# FaderBay.net
KiCad netlist of a schematic drawn in EasyEDA Pro
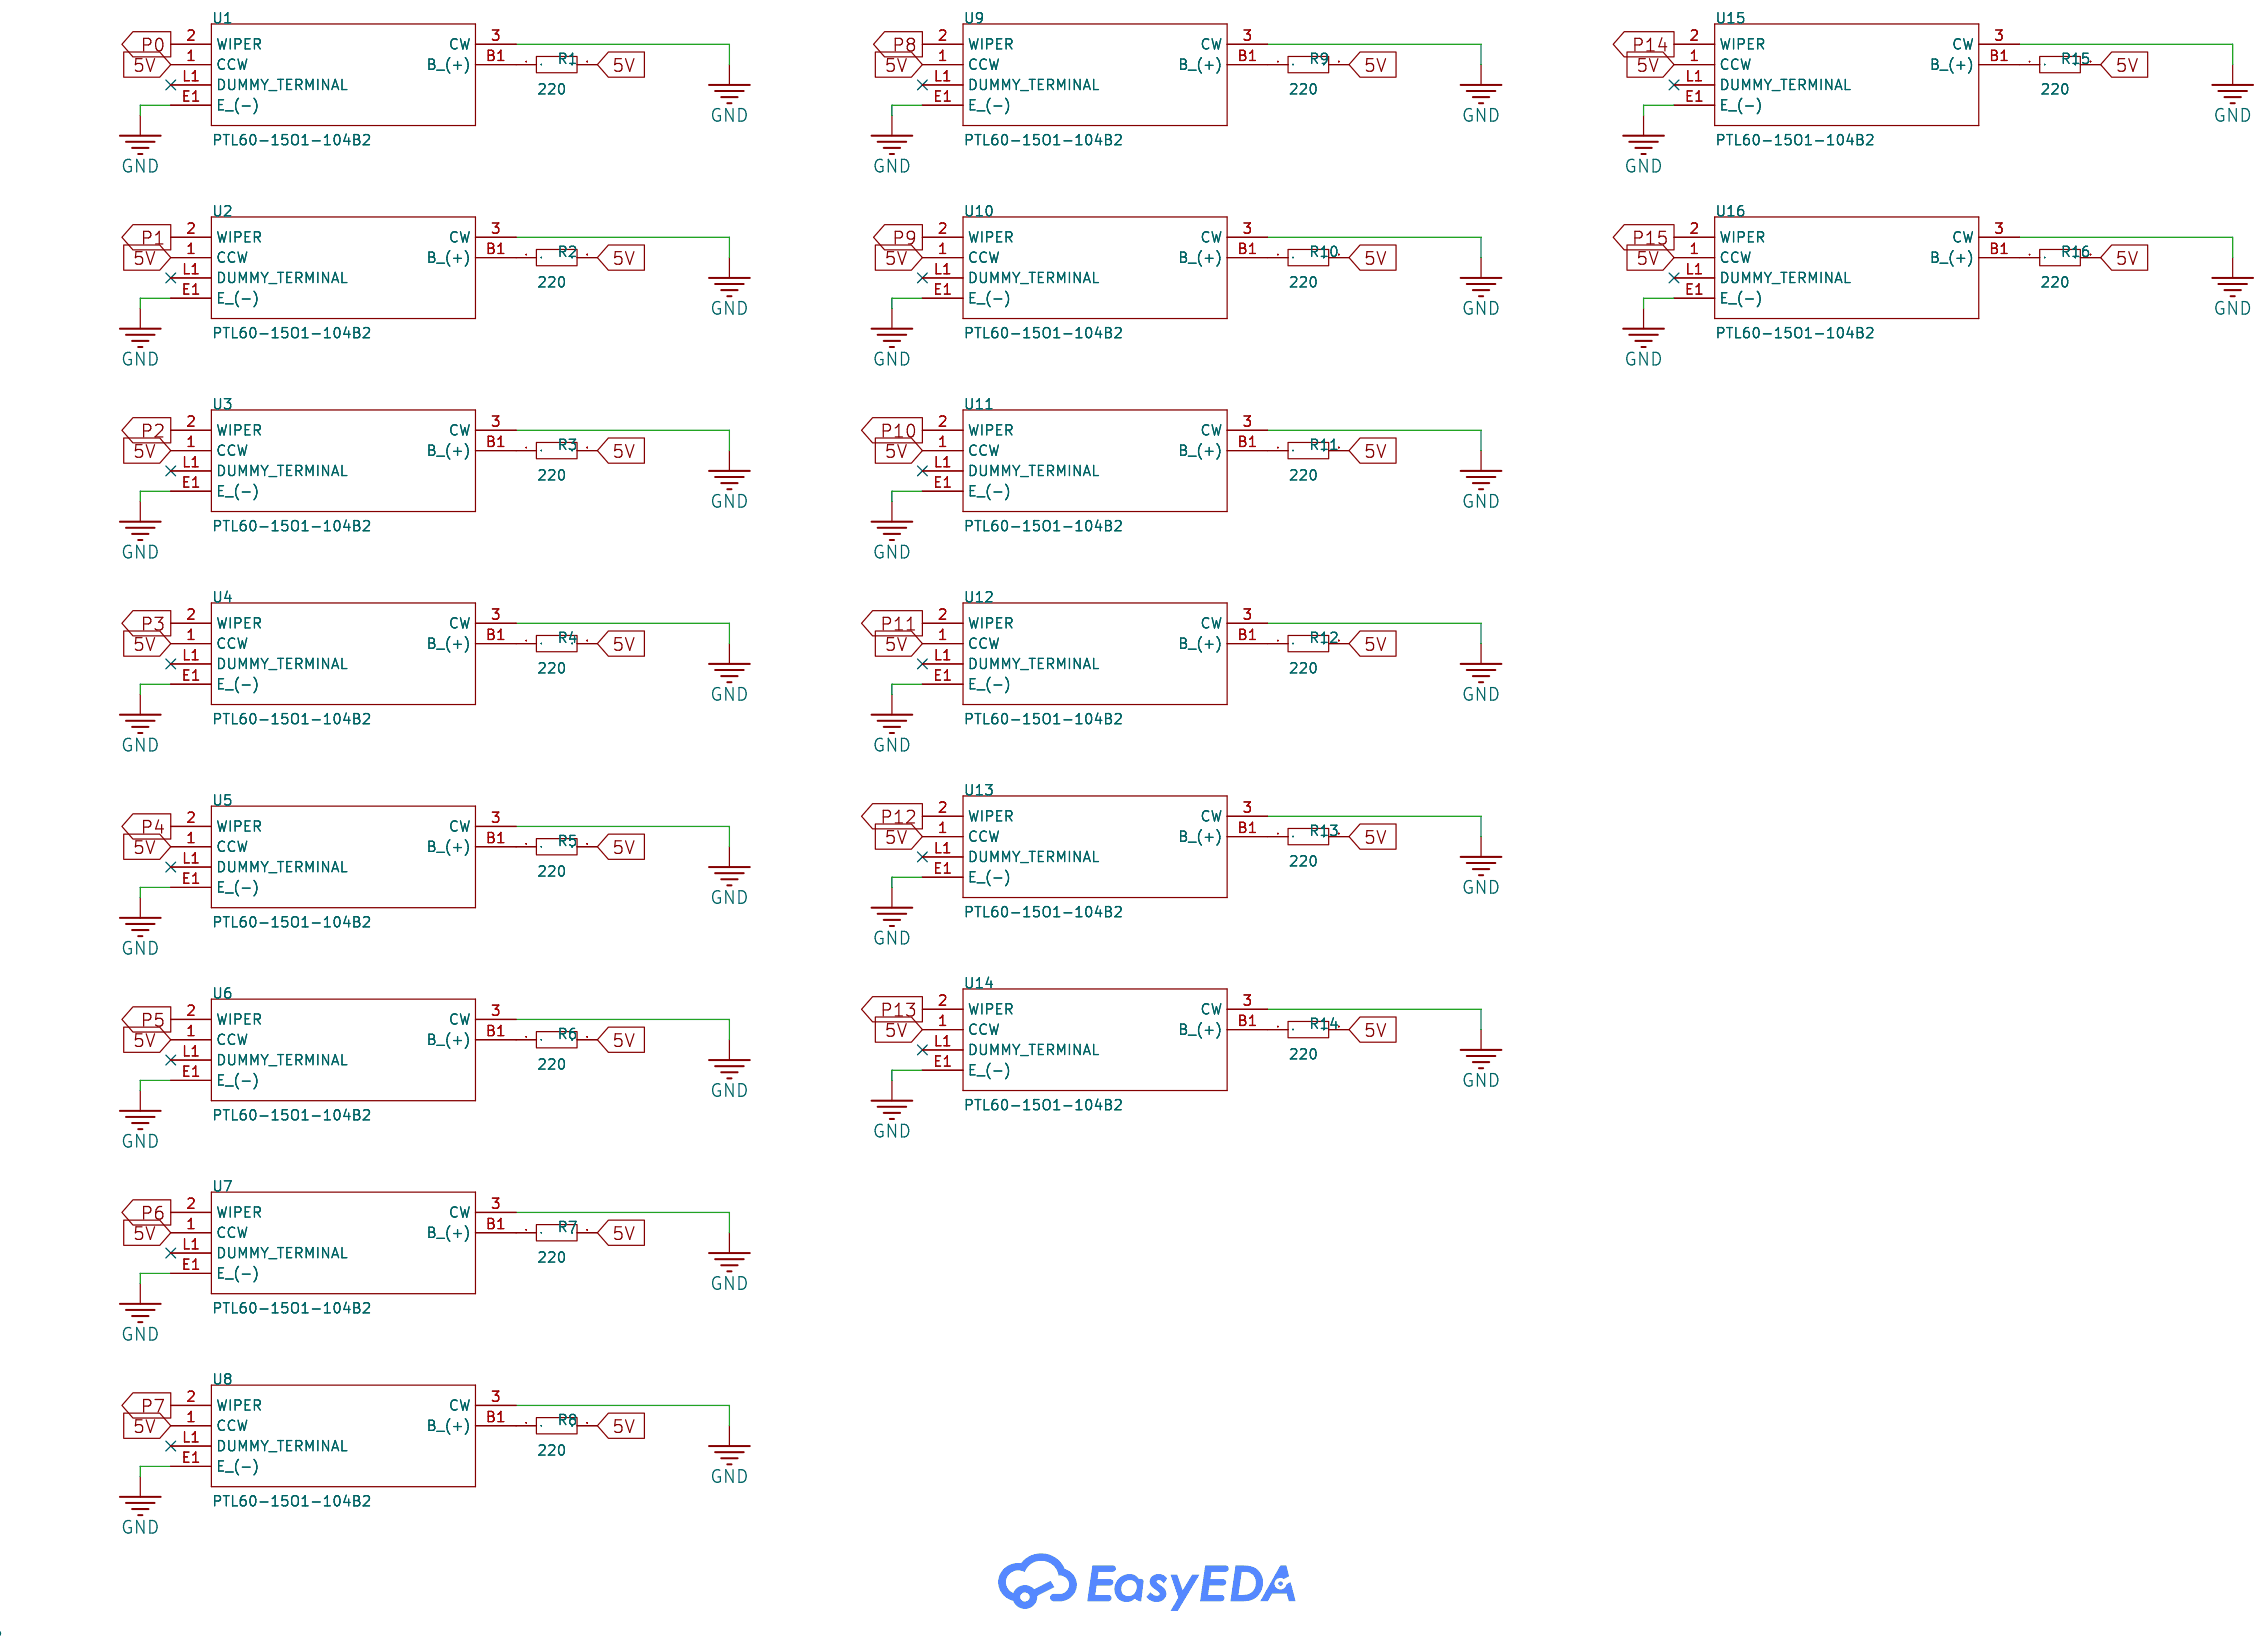
[diagram p0: P1]
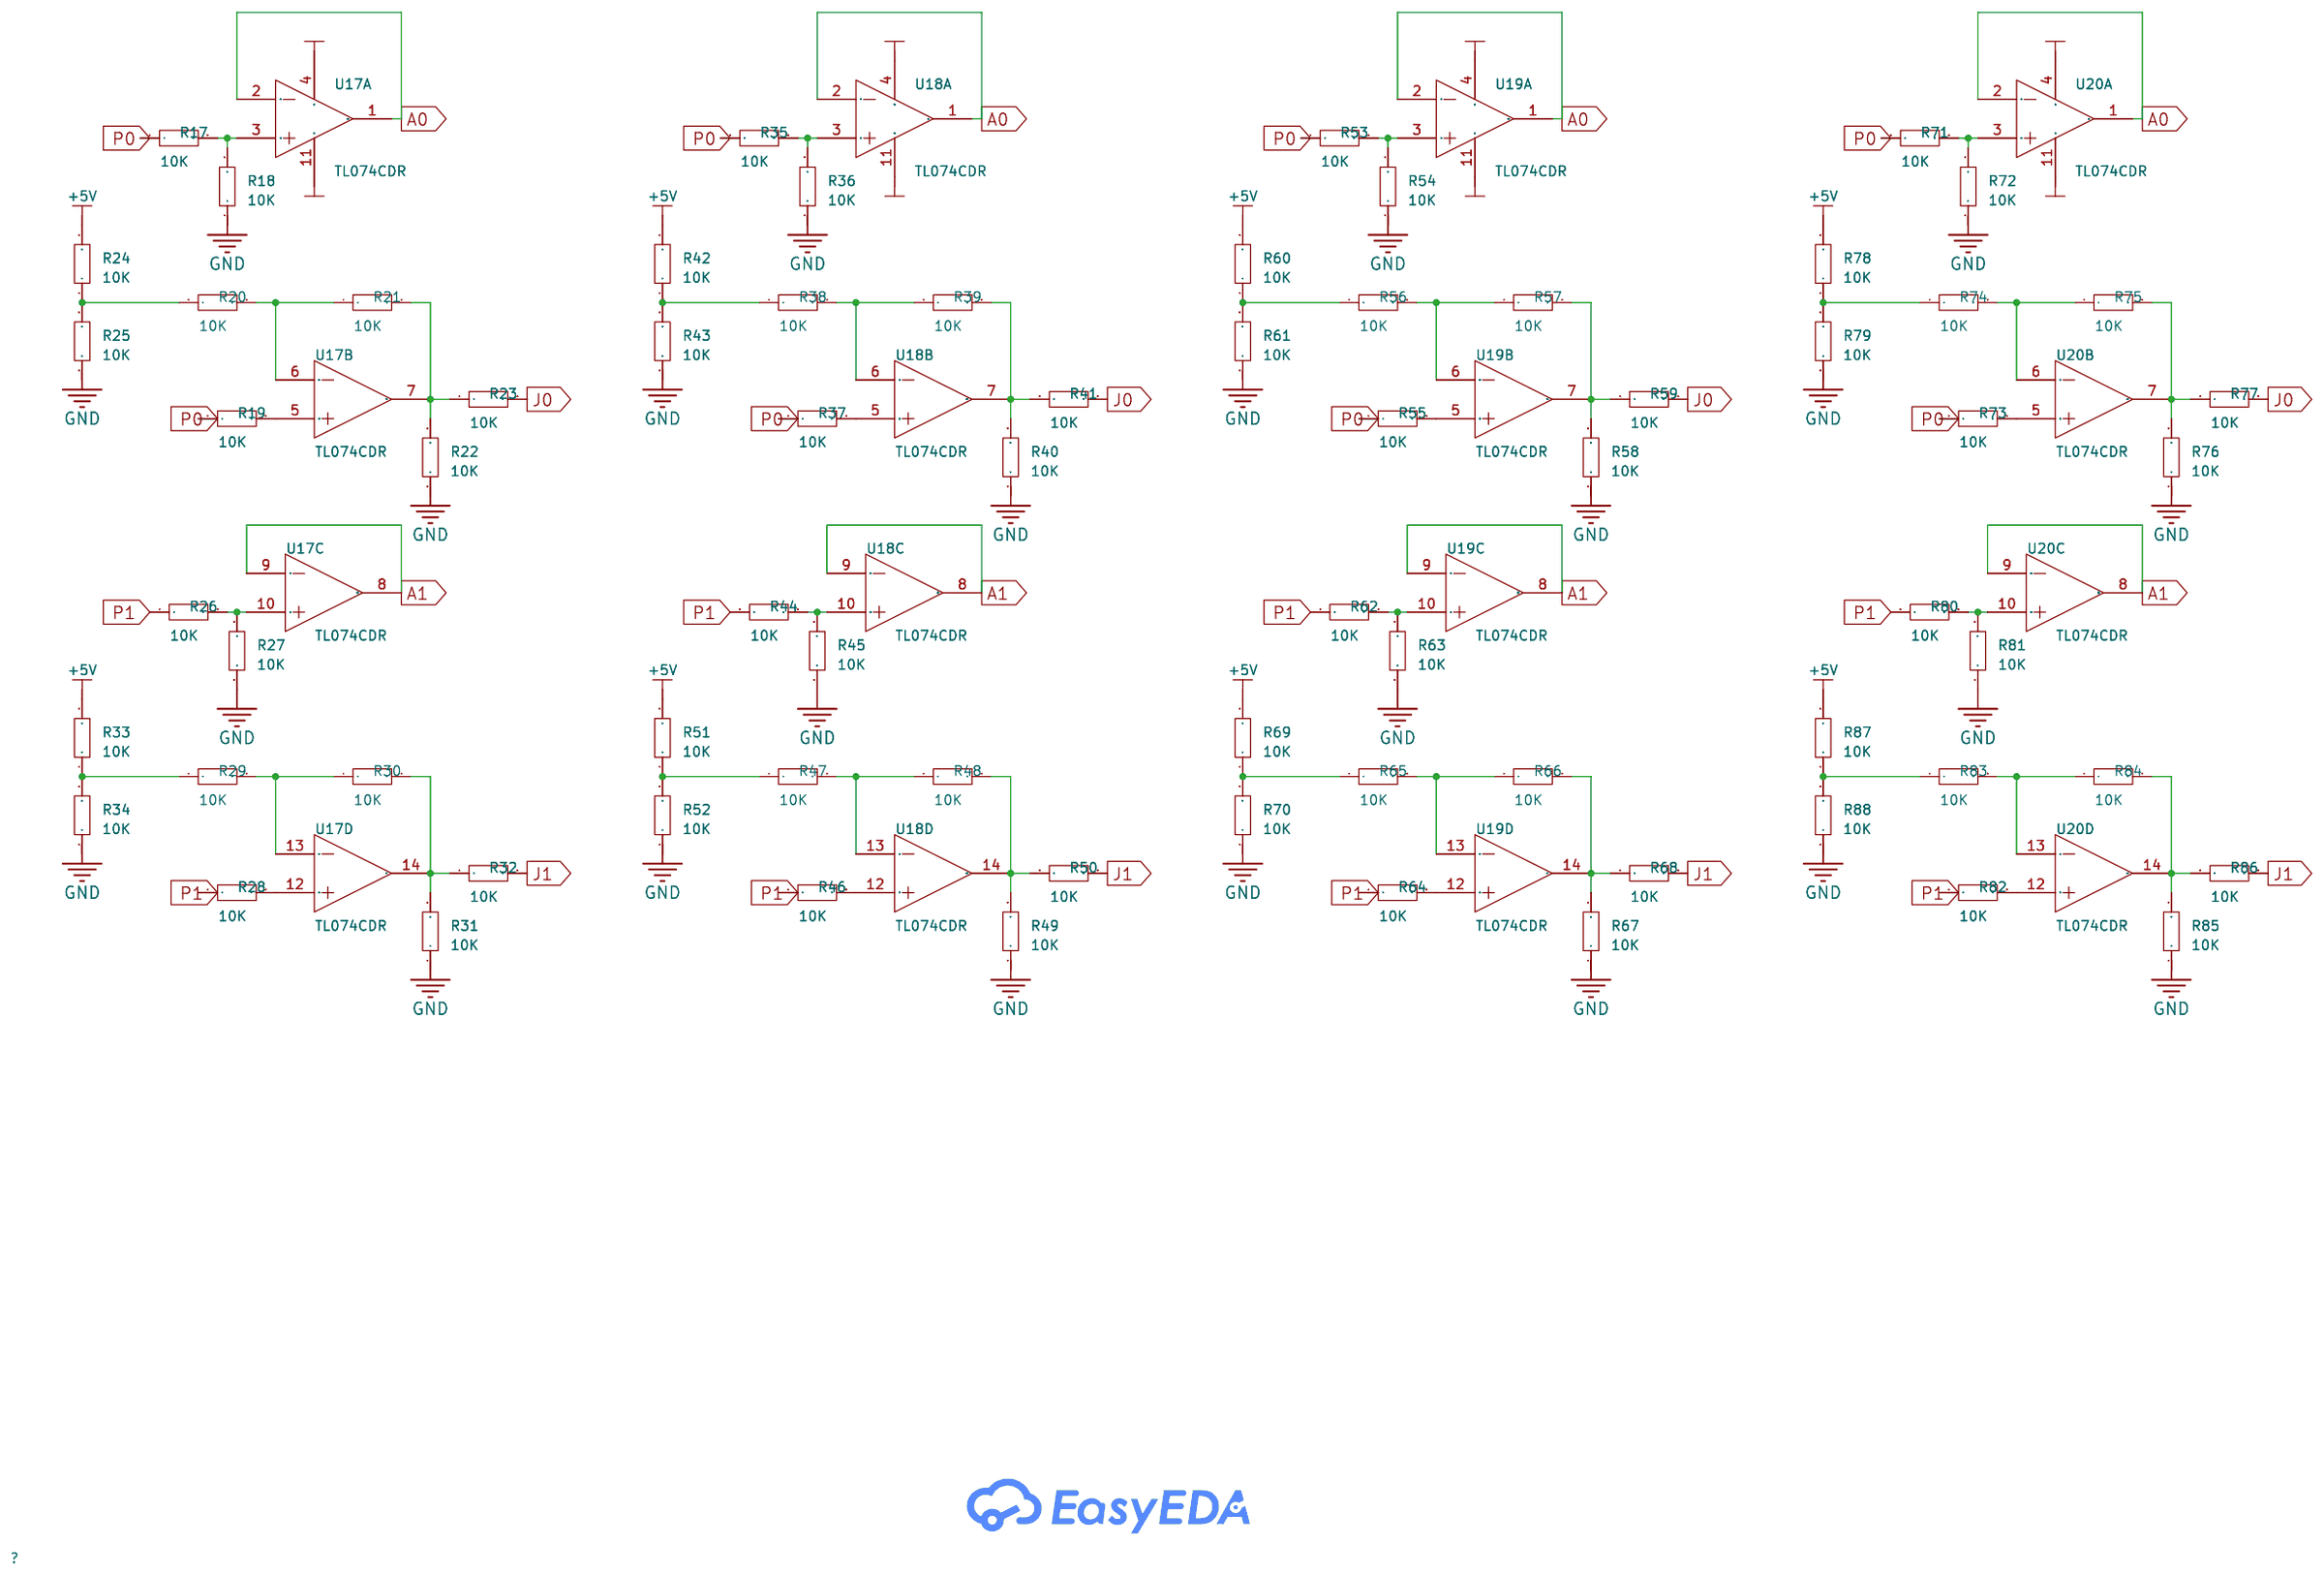
[diagram p1: P2]
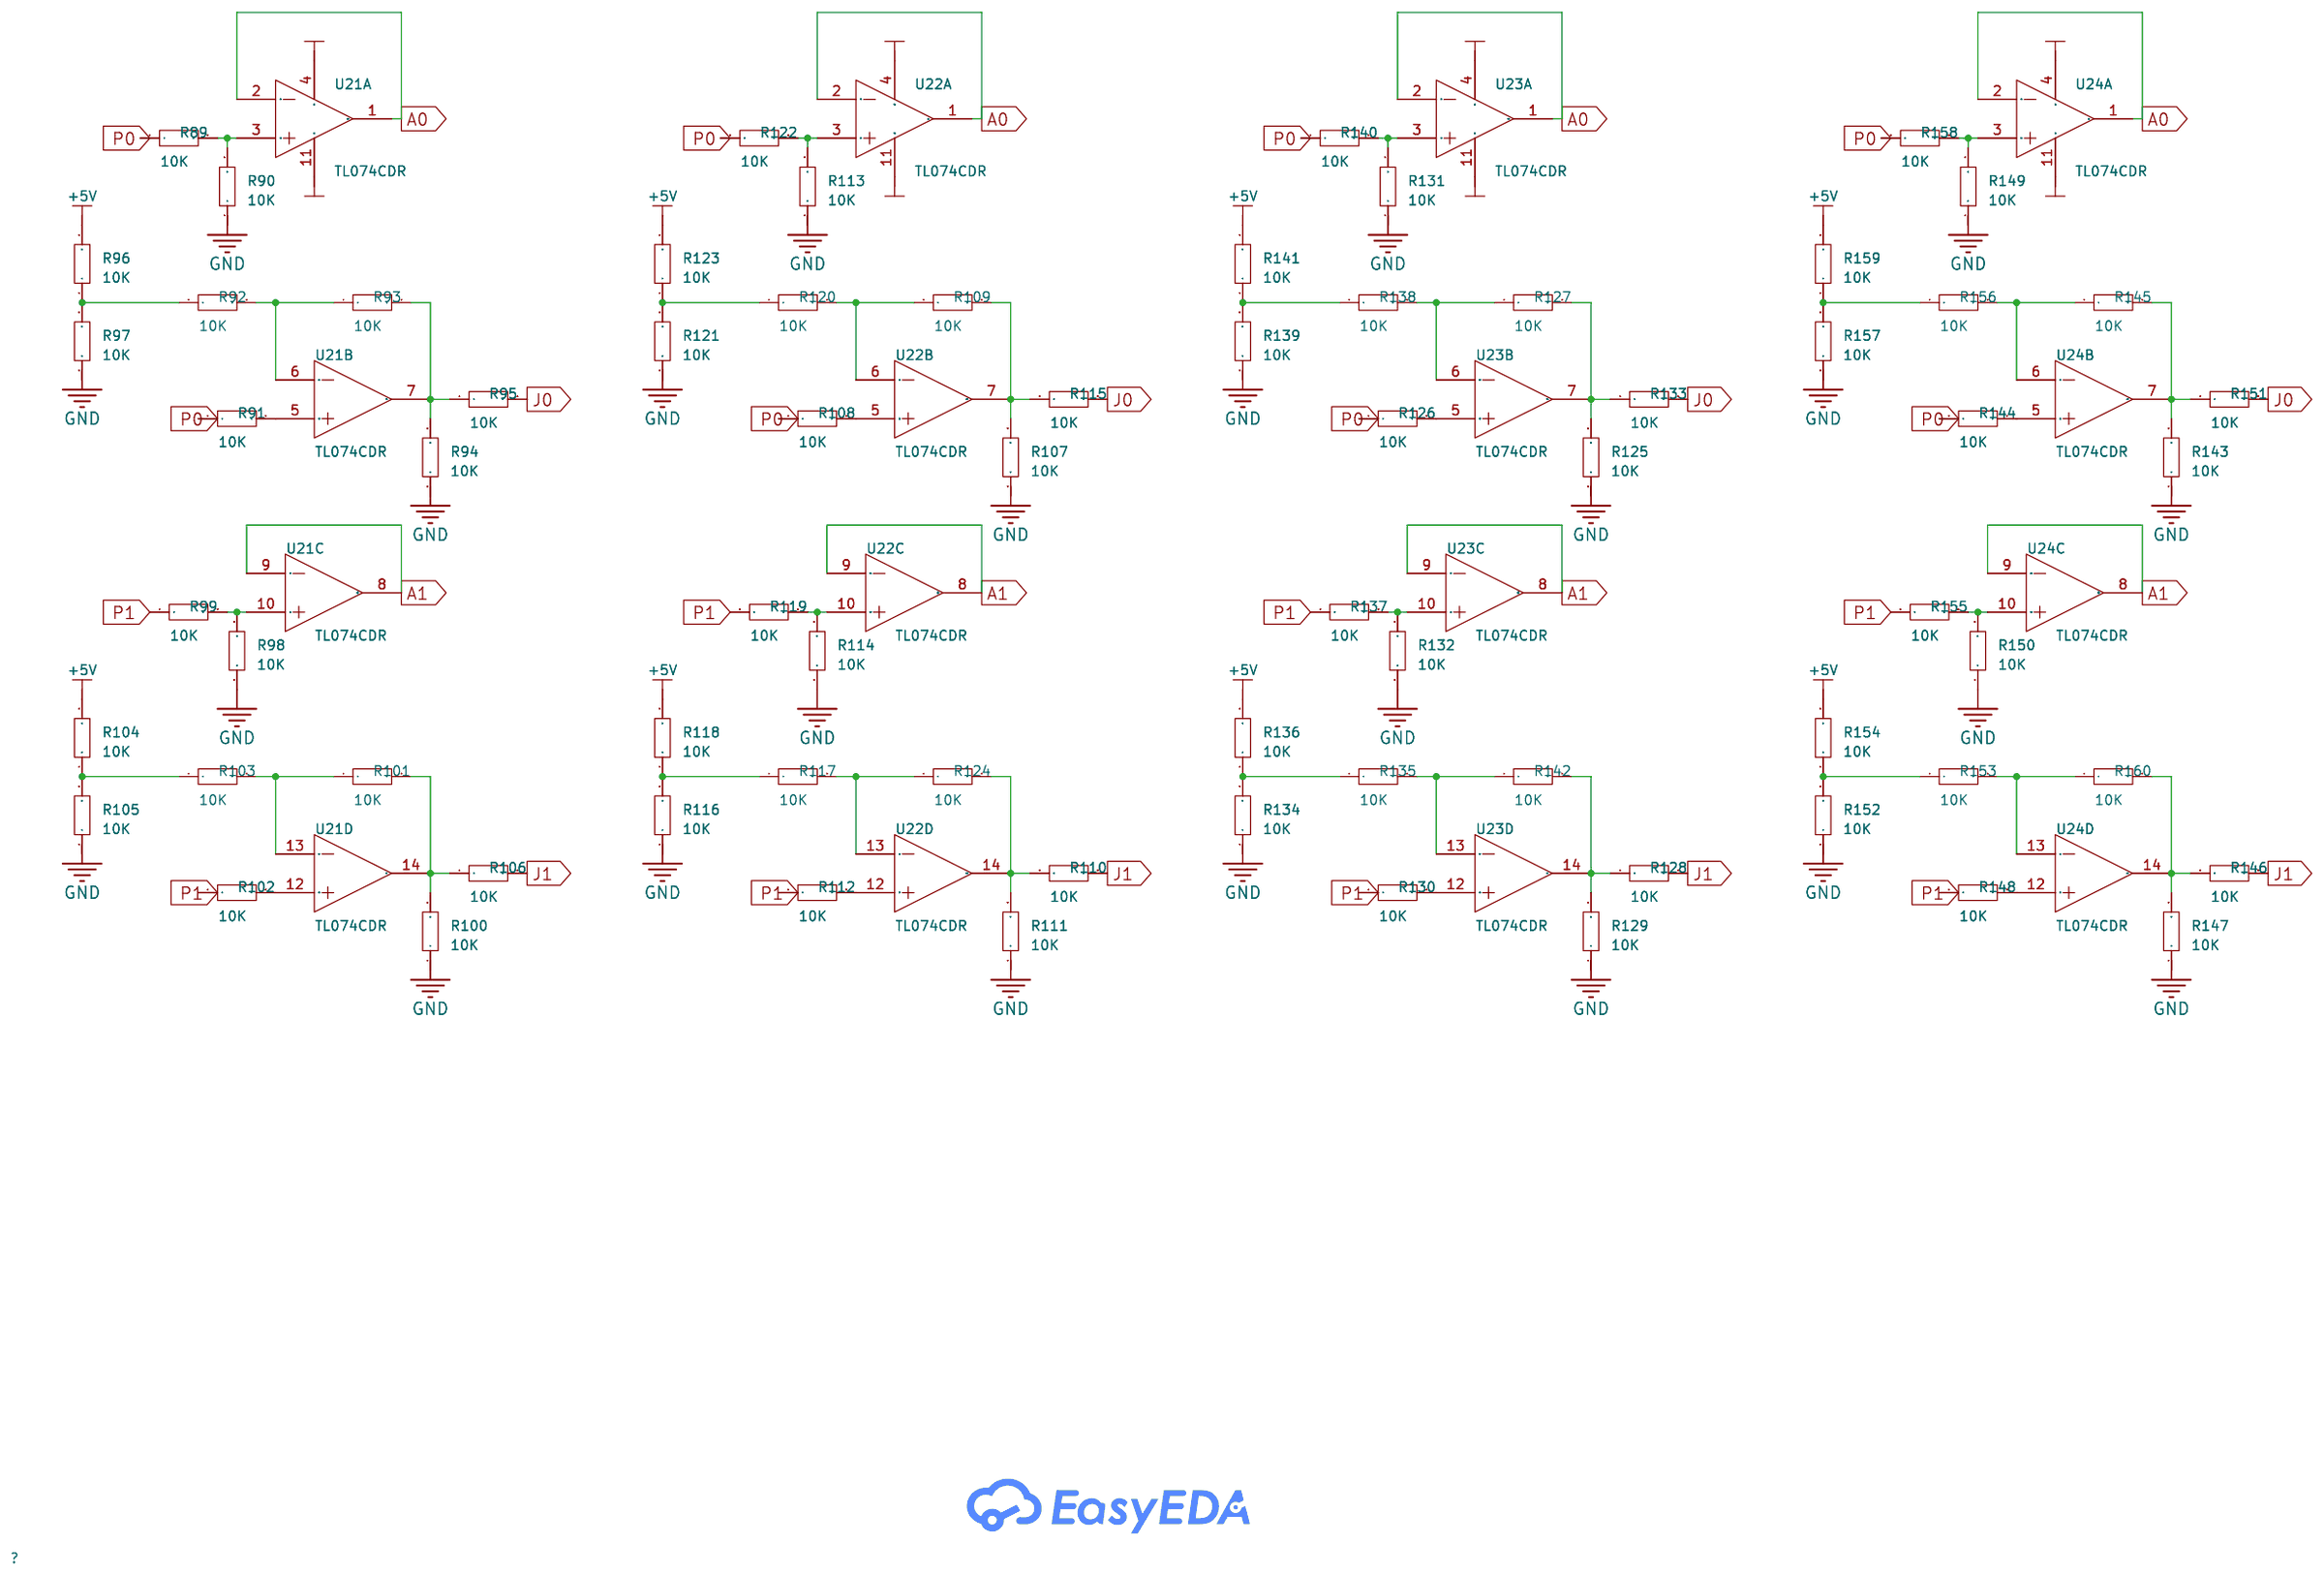
[diagram p2: P3]

(export (version "E")
  (design (tool "Eeschema 10.0.6"))
  (components
    (comp (ref "R1") (value "220") (footprint "easyedapro:R0603") (libsource (lib "easyedapro") (part "Res")))
    (comp (ref "R2") (value "220") (footprint "easyedapro:R0603") (libsource (lib "easyedapro") (part "Res")))
    (comp (ref "R3") (value "220") (footprint "easyedapro:R0603") (libsource (lib "easyedapro") (part "Res")))
    (comp (ref "R4") (value "220") (footprint "easyedapro:R0603") (libsource (lib "easyedapro") (part "Res")))
    (comp (ref "R5") (value "220") (footprint "easyedapro:R0603") (libsource (lib "easyedapro") (part "Res")))
    (comp (ref "R6") (value "220") (footprint "easyedapro:R0603") (libsource (lib "easyedapro") (part "Res")))
    (comp (ref "R7") (value "220") (footprint "easyedapro:R0603") (libsource (lib "easyedapro") (part "Res")))
    (comp (ref "R8") (value "220") (footprint "easyedapro:R0603") (libsource (lib "easyedapro") (part "Res")))
    (comp (ref "R9") (value "220") (footprint "easyedapro:R0603") (libsource (lib "easyedapro") (part "Res")))
    (comp (ref "R10")
      (value "220")
      (footprint "easyedapro:R0603")
      (libsource (lib "easyedapro") (part "Res"))
    )
    (comp (ref "R11")
      (value "220")
      (footprint "easyedapro:R0603")
      (libsource (lib "easyedapro") (part "Res"))
    )
    (comp (ref "R12")
      (value "220")
      (footprint "easyedapro:R0603")
      (libsource (lib "easyedapro") (part "Res"))
    )
    (comp (ref "R13")
      (value "220")
      (footprint "easyedapro:R0603")
      (libsource (lib "easyedapro") (part "Res"))
    )
    (comp (ref "R14")
      (value "220")
      (footprint "easyedapro:R0603")
      (libsource (lib "easyedapro") (part "Res"))
    )
    (comp (ref "R15")
      (value "220")
      (footprint "easyedapro:R0603")
      (libsource (lib "easyedapro") (part "Res"))
    )
    (comp (ref "R16")
      (value "220")
      (footprint "easyedapro:R0603")
      (libsource (lib "easyedapro") (part "Res"))
    )
    (comp (ref "U1")
      (value "PTL60-15O1-104B2")
      (footprint "easyedapro:PTL6015O1104B2")
      (libsource (lib "easyedapro") (part "PTL60-15O1-104B2"))
    )
    (comp (ref "U2")
      (value "PTL60-15O1-104B2")
      (footprint "easyedapro:PTL6015O1104B2")
      (libsource (lib "easyedapro") (part "PTL60-15O1-104B2"))
    )
    (comp (ref "U3")
      (value "PTL60-15O1-104B2")
      (footprint "easyedapro:PTL6015O1104B2")
      (libsource (lib "easyedapro") (part "PTL60-15O1-104B2"))
    )
    (comp (ref "U4")
      (value "PTL60-15O1-104B2")
      (footprint "easyedapro:PTL6015O1104B2")
      (libsource (lib "easyedapro") (part "PTL60-15O1-104B2"))
    )
    (comp (ref "U5")
      (value "PTL60-15O1-104B2")
      (footprint "easyedapro:PTL6015O1104B2")
      (libsource (lib "easyedapro") (part "PTL60-15O1-104B2"))
    )
    (comp (ref "U6")
      (value "PTL60-15O1-104B2")
      (footprint "easyedapro:PTL6015O1104B2")
      (libsource (lib "easyedapro") (part "PTL60-15O1-104B2"))
    )
    (comp (ref "U7")
      (value "PTL60-15O1-104B2")
      (footprint "easyedapro:PTL6015O1104B2")
      (libsource (lib "easyedapro") (part "PTL60-15O1-104B2"))
    )
    (comp (ref "U8")
      (value "PTL60-15O1-104B2")
      (footprint "easyedapro:PTL6015O1104B2")
      (libsource (lib "easyedapro") (part "PTL60-15O1-104B2"))
    )
    (comp (ref "U9")
      (value "PTL60-15O1-104B2")
      (footprint "easyedapro:PTL6015O1104B2")
      (libsource (lib "easyedapro") (part "PTL60-15O1-104B2"))
    )
    (comp (ref "U10")
      (value "PTL60-15O1-104B2")
      (footprint "easyedapro:PTL6015O1104B2")
      (libsource (lib "easyedapro") (part "PTL60-15O1-104B2"))
    )
    (comp (ref "U11")
      (value "PTL60-15O1-104B2")
      (footprint "easyedapro:PTL6015O1104B2")
      (libsource (lib "easyedapro") (part "PTL60-15O1-104B2"))
    )
    (comp (ref "U12")
      (value "PTL60-15O1-104B2")
      (footprint "easyedapro:PTL6015O1104B2")
      (libsource (lib "easyedapro") (part "PTL60-15O1-104B2"))
    )
    (comp (ref "U13")
      (value "PTL60-15O1-104B2")
      (footprint "easyedapro:PTL6015O1104B2")
      (libsource (lib "easyedapro") (part "PTL60-15O1-104B2"))
    )
    (comp (ref "U14")
      (value "PTL60-15O1-104B2")
      (footprint "easyedapro:PTL6015O1104B2")
      (libsource (lib "easyedapro") (part "PTL60-15O1-104B2"))
    )
    (comp (ref "U15")
      (value "PTL60-15O1-104B2")
      (footprint "easyedapro:PTL6015O1104B2")
      (libsource (lib "easyedapro") (part "PTL60-15O1-104B2"))
    )
    (comp (ref "U16")
      (value "PTL60-15O1-104B2")
      (footprint "easyedapro:PTL6015O1104B2")
      (libsource (lib "easyedapro") (part "PTL60-15O1-104B2"))
    )
    (comp (ref "R17")
      (value "10K")
      (footprint "easyedapro:R0603")
      (libsource (lib "easyedapro") (part "Res"))
    )
    (comp (ref "R18")
      (value "10K")
      (footprint "easyedapro:R0603")
      (libsource (lib "easyedapro") (part "Res"))
    )
    (comp (ref "R19")
      (value "10K")
      (footprint "easyedapro:R0603")
      (libsource (lib "easyedapro") (part "Res"))
    )
    (comp (ref "R20")
      (value "10K")
      (footprint "easyedapro:R0603")
      (libsource (lib "easyedapro") (part "Res"))
    )
    (comp (ref "R21")
      (value "10K")
      (footprint "easyedapro:R0603")
      (libsource (lib "easyedapro") (part "Res"))
    )
    (comp (ref "R22")
      (value "10K")
      (footprint "easyedapro:R0603")
      (libsource (lib "easyedapro") (part "Res"))
    )
    (comp (ref "R23")
      (value "10K")
      (footprint "easyedapro:R0603")
      (libsource (lib "easyedapro") (part "Res"))
    )
    (comp (ref "R24")
      (value "10K")
      (footprint "easyedapro:R0603")
      (libsource (lib "easyedapro") (part "Res"))
    )
    (comp (ref "R25")
      (value "10K")
      (footprint "easyedapro:R0603")
      (libsource (lib "easyedapro") (part "Res"))
    )
    (comp (ref "R26")
      (value "10K")
      (footprint "easyedapro:R0603")
      (libsource (lib "easyedapro") (part "Res"))
    )
    (comp (ref "R27")
      (value "10K")
      (footprint "easyedapro:R0603")
      (libsource (lib "easyedapro") (part "Res"))
    )
    (comp (ref "R28")
      (value "10K")
      (footprint "easyedapro:R0603")
      (libsource (lib "easyedapro") (part "Res"))
    )
    (comp (ref "R29")
      (value "10K")
      (footprint "easyedapro:R0603")
      (libsource (lib "easyedapro") (part "Res"))
    )
    (comp (ref "R30")
      (value "10K")
      (footprint "easyedapro:R0603")
      (libsource (lib "easyedapro") (part "Res"))
    )
    (comp (ref "R31")
      (value "10K")
      (footprint "easyedapro:R0603")
      (libsource (lib "easyedapro") (part "Res"))
    )
    (comp (ref "R32")
      (value "10K")
      (footprint "easyedapro:R0603")
      (libsource (lib "easyedapro") (part "Res"))
    )
    (comp (ref "R33")
      (value "10K")
      (footprint "easyedapro:R0603")
      (libsource (lib "easyedapro") (part "Res"))
    )
    (comp (ref "R34")
      (value "10K")
      (footprint "easyedapro:R0603")
      (libsource (lib "easyedapro") (part "Res"))
    )
    (comp (ref "R35")
      (value "10K")
      (footprint "easyedapro:R0603")
      (libsource (lib "easyedapro") (part "Res"))
    )
    (comp (ref "R36")
      (value "10K")
      (footprint "easyedapro:R0603")
      (libsource (lib "easyedapro") (part "Res"))
    )
    (comp (ref "R37")
      (value "10K")
      (footprint "easyedapro:R0603")
      (libsource (lib "easyedapro") (part "Res"))
    )
    (comp (ref "R38")
      (value "10K")
      (footprint "easyedapro:R0603")
      (libsource (lib "easyedapro") (part "Res"))
    )
    (comp (ref "R39")
      (value "10K")
      (footprint "easyedapro:R0603")
      (libsource (lib "easyedapro") (part "Res"))
    )
    (comp (ref "R40")
      (value "10K")
      (footprint "easyedapro:R0603")
      (libsource (lib "easyedapro") (part "Res"))
    )
    (comp (ref "R41")
      (value "10K")
      (footprint "easyedapro:R0603")
      (libsource (lib "easyedapro") (part "Res"))
    )
    (comp (ref "R42")
      (value "10K")
      (footprint "easyedapro:R0603")
      (libsource (lib "easyedapro") (part "Res"))
    )
    (comp (ref "R43")
      (value "10K")
      (footprint "easyedapro:R0603")
      (libsource (lib "easyedapro") (part "Res"))
    )
    (comp (ref "R44")
      (value "10K")
      (footprint "easyedapro:R0603")
      (libsource (lib "easyedapro") (part "Res"))
    )
    (comp (ref "R45")
      (value "10K")
      (footprint "easyedapro:R0603")
      (libsource (lib "easyedapro") (part "Res"))
    )
    (comp (ref "R46")
      (value "10K")
      (footprint "easyedapro:R0603")
      (libsource (lib "easyedapro") (part "Res"))
    )
    (comp (ref "R47")
      (value "10K")
      (footprint "easyedapro:R0603")
      (libsource (lib "easyedapro") (part "Res"))
    )
    (comp (ref "R48")
      (value "10K")
      (footprint "easyedapro:R0603")
      (libsource (lib "easyedapro") (part "Res"))
    )
    (comp (ref "R49")
      (value "10K")
      (footprint "easyedapro:R0603")
      (libsource (lib "easyedapro") (part "Res"))
    )
    (comp (ref "R50")
      (value "10K")
      (footprint "easyedapro:R0603")
      (libsource (lib "easyedapro") (part "Res"))
    )
    (comp (ref "R51")
      (value "10K")
      (footprint "easyedapro:R0603")
      (libsource (lib "easyedapro") (part "Res"))
    )
    (comp (ref "R52")
      (value "10K")
      (footprint "easyedapro:R0603")
      (libsource (lib "easyedapro") (part "Res"))
    )
    (comp (ref "R53")
      (value "10K")
      (footprint "easyedapro:R0603")
      (libsource (lib "easyedapro") (part "Res"))
    )
    (comp (ref "R54")
      (value "10K")
      (footprint "easyedapro:R0603")
      (libsource (lib "easyedapro") (part "Res"))
    )
    (comp (ref "R55")
      (value "10K")
      (footprint "easyedapro:R0603")
      (libsource (lib "easyedapro") (part "Res"))
    )
    (comp (ref "R56")
      (value "10K")
      (footprint "easyedapro:R0603")
      (libsource (lib "easyedapro") (part "Res"))
    )
    (comp (ref "R57")
      (value "10K")
      (footprint "easyedapro:R0603")
      (libsource (lib "easyedapro") (part "Res"))
    )
    (comp (ref "R58")
      (value "10K")
      (footprint "easyedapro:R0603")
      (libsource (lib "easyedapro") (part "Res"))
    )
    (comp (ref "R59")
      (value "10K")
      (footprint "easyedapro:R0603")
      (libsource (lib "easyedapro") (part "Res"))
    )
    (comp (ref "R60")
      (value "10K")
      (footprint "easyedapro:R0603")
      (libsource (lib "easyedapro") (part "Res"))
    )
    (comp (ref "R61")
      (value "10K")
      (footprint "easyedapro:R0603")
      (libsource (lib "easyedapro") (part "Res"))
    )
    (comp (ref "R62")
      (value "10K")
      (footprint "easyedapro:R0603")
      (libsource (lib "easyedapro") (part "Res"))
    )
    (comp (ref "R63")
      (value "10K")
      (footprint "easyedapro:R0603")
      (libsource (lib "easyedapro") (part "Res"))
    )
    (comp (ref "R64")
      (value "10K")
      (footprint "easyedapro:R0603")
      (libsource (lib "easyedapro") (part "Res"))
    )
    (comp (ref "R65")
      (value "10K")
      (footprint "easyedapro:R0603")
      (libsource (lib "easyedapro") (part "Res"))
    )
    (comp (ref "R66")
      (value "10K")
      (footprint "easyedapro:R0603")
      (libsource (lib "easyedapro") (part "Res"))
    )
    (comp (ref "R67")
      (value "10K")
      (footprint "easyedapro:R0603")
      (libsource (lib "easyedapro") (part "Res"))
    )
    (comp (ref "R68")
      (value "10K")
      (footprint "easyedapro:R0603")
      (libsource (lib "easyedapro") (part "Res"))
    )
    (comp (ref "R69")
      (value "10K")
      (footprint "easyedapro:R0603")
      (libsource (lib "easyedapro") (part "Res"))
    )
    (comp (ref "R70")
      (value "10K")
      (footprint "easyedapro:R0603")
      (libsource (lib "easyedapro") (part "Res"))
    )
    (comp (ref "R71")
      (value "10K")
      (footprint "easyedapro:R0603")
      (libsource (lib "easyedapro") (part "Res"))
    )
    (comp (ref "R72")
      (value "10K")
      (footprint "easyedapro:R0603")
      (libsource (lib "easyedapro") (part "Res"))
    )
    (comp (ref "R73")
      (value "10K")
      (footprint "easyedapro:R0603")
      (libsource (lib "easyedapro") (part "Res"))
    )
    (comp (ref "R74")
      (value "10K")
      (footprint "easyedapro:R0603")
      (libsource (lib "easyedapro") (part "Res"))
    )
    (comp (ref "R75")
      (value "10K")
      (footprint "easyedapro:R0603")
      (libsource (lib "easyedapro") (part "Res"))
    )
    (comp (ref "R76")
      (value "10K")
      (footprint "easyedapro:R0603")
      (libsource (lib "easyedapro") (part "Res"))
    )
    (comp (ref "R77")
      (value "10K")
      (footprint "easyedapro:R0603")
      (libsource (lib "easyedapro") (part "Res"))
    )
    (comp (ref "R78")
      (value "10K")
      (footprint "easyedapro:R0603")
      (libsource (lib "easyedapro") (part "Res"))
    )
    (comp (ref "R79")
      (value "10K")
      (footprint "easyedapro:R0603")
      (libsource (lib "easyedapro") (part "Res"))
    )
    (comp (ref "R80")
      (value "10K")
      (footprint "easyedapro:R0603")
      (libsource (lib "easyedapro") (part "Res"))
    )
    (comp (ref "R81")
      (value "10K")
      (footprint "easyedapro:R0603")
      (libsource (lib "easyedapro") (part "Res"))
    )
    (comp (ref "R82")
      (value "10K")
      (footprint "easyedapro:R0603")
      (libsource (lib "easyedapro") (part "Res"))
    )
    (comp (ref "R83")
      (value "10K")
      (footprint "easyedapro:R0603")
      (libsource (lib "easyedapro") (part "Res"))
    )
    (comp (ref "R84")
      (value "10K")
      (footprint "easyedapro:R0603")
      (libsource (lib "easyedapro") (part "Res"))
    )
    (comp (ref "R85")
      (value "10K")
      (footprint "easyedapro:R0603")
      (libsource (lib "easyedapro") (part "Res"))
    )
    (comp (ref "R86")
      (value "10K")
      (footprint "easyedapro:R0603")
      (libsource (lib "easyedapro") (part "Res"))
    )
    (comp (ref "R87")
      (value "10K")
      (footprint "easyedapro:R0603")
      (libsource (lib "easyedapro") (part "Res"))
    )
    (comp (ref "R88")
      (value "10K")
      (footprint "easyedapro:R0603")
      (libsource (lib "easyedapro") (part "Res"))
    )
    (comp (ref "U17")
      (value "TL074CDR")
      (footprint "easyedapro:SOIC-14_L8.7-W3.9-P1.27-LS6.0-BL")
      (fields (field (name "Manufacturer") "TI(德州仪器)"))
      (libsource (lib "easyedapro") (part "TL074CDR"))
    )
    (comp (ref "U18")
      (value "TL074CDR")
      (footprint "easyedapro:SOIC-14_L8.7-W3.9-P1.27-LS6.0-BL")
      (fields (field (name "Manufacturer") "TI(德州仪器)"))
      (libsource (lib "easyedapro") (part "TL074CDR"))
    )
    (comp (ref "U19")
      (value "TL074CDR")
      (footprint "easyedapro:SOIC-14_L8.7-W3.9-P1.27-LS6.0-BL")
      (fields (field (name "Manufacturer") "TI(德州仪器)"))
      (libsource (lib "easyedapro") (part "TL074CDR"))
    )
    (comp (ref "U20")
      (value "TL074CDR")
      (footprint "easyedapro:SOIC-14_L8.7-W3.9-P1.27-LS6.0-BL")
      (fields (field (name "Manufacturer") "TI(德州仪器)"))
      (libsource (lib "easyedapro") (part "TL074CDR"))
    )
    (comp (ref "R89")
      (value "10K")
      (footprint "easyedapro:R0603")
      (libsource (lib "easyedapro") (part "Res"))
    )
    (comp (ref "R90")
      (value "10K")
      (footprint "easyedapro:R0603")
      (libsource (lib "easyedapro") (part "Res"))
    )
    (comp (ref "R91")
      (value "10K")
      (footprint "easyedapro:R0603")
      (libsource (lib "easyedapro") (part "Res"))
    )
    (comp (ref "R92")
      (value "10K")
      (footprint "easyedapro:R0603")
      (libsource (lib "easyedapro") (part "Res"))
    )
    (comp (ref "R93")
      (value "10K")
      (footprint "easyedapro:R0603")
      (libsource (lib "easyedapro") (part "Res"))
    )
    (comp (ref "R94")
      (value "10K")
      (footprint "easyedapro:R0603")
      (libsource (lib "easyedapro") (part "Res"))
    )
    (comp (ref "R95")
      (value "10K")
      (footprint "easyedapro:R0603")
      (libsource (lib "easyedapro") (part "Res"))
    )
    (comp (ref "R96")
      (value "10K")
      (footprint "easyedapro:R0603")
      (libsource (lib "easyedapro") (part "Res"))
    )
    (comp (ref "R97")
      (value "10K")
      (footprint "easyedapro:R0603")
      (libsource (lib "easyedapro") (part "Res"))
    )
    (comp (ref "R98")
      (value "10K")
      (footprint "easyedapro:R0603")
      (libsource (lib "easyedapro") (part "Res"))
    )
    (comp (ref "R99")
      (value "10K")
      (footprint "easyedapro:R0603")
      (libsource (lib "easyedapro") (part "Res"))
    )
    (comp (ref "R100")
      (value "10K")
      (footprint "easyedapro:R0603")
      (libsource (lib "easyedapro") (part "Res"))
    )
    (comp (ref "R101")
      (value "10K")
      (footprint "easyedapro:R0603")
      (libsource (lib "easyedapro") (part "Res"))
    )
    (comp (ref "R102")
      (value "10K")
      (footprint "easyedapro:R0603")
      (libsource (lib "easyedapro") (part "Res"))
    )
    (comp (ref "R103")
      (value "10K")
      (footprint "easyedapro:R0603")
      (libsource (lib "easyedapro") (part "Res"))
    )
    (comp (ref "R104")
      (value "10K")
      (footprint "easyedapro:R0603")
      (libsource (lib "easyedapro") (part "Res"))
    )
    (comp (ref "R105")
      (value "10K")
      (footprint "easyedapro:R0603")
      (libsource (lib "easyedapro") (part "Res"))
    )
    (comp (ref "R106")
      (value "10K")
      (footprint "easyedapro:R0603")
      (libsource (lib "easyedapro") (part "Res"))
    )
    (comp (ref "R107")
      (value "10K")
      (footprint "easyedapro:R0603")
      (libsource (lib "easyedapro") (part "Res"))
    )
    (comp (ref "R108")
      (value "10K")
      (footprint "easyedapro:R0603")
      (libsource (lib "easyedapro") (part "Res"))
    )
    (comp (ref "R109")
      (value "10K")
      (footprint "easyedapro:R0603")
      (libsource (lib "easyedapro") (part "Res"))
    )
    (comp (ref "R110")
      (value "10K")
      (footprint "easyedapro:R0603")
      (libsource (lib "easyedapro") (part "Res"))
    )
    (comp (ref "R111")
      (value "10K")
      (footprint "easyedapro:R0603")
      (libsource (lib "easyedapro") (part "Res"))
    )
    (comp (ref "R112")
      (value "10K")
      (footprint "easyedapro:R0603")
      (libsource (lib "easyedapro") (part "Res"))
    )
    (comp (ref "R113")
      (value "10K")
      (footprint "easyedapro:R0603")
      (libsource (lib "easyedapro") (part "Res"))
    )
    (comp (ref "R114")
      (value "10K")
      (footprint "easyedapro:R0603")
      (libsource (lib "easyedapro") (part "Res"))
    )
    (comp (ref "R115")
      (value "10K")
      (footprint "easyedapro:R0603")
      (libsource (lib "easyedapro") (part "Res"))
    )
    (comp (ref "R116")
      (value "10K")
      (footprint "easyedapro:R0603")
      (libsource (lib "easyedapro") (part "Res"))
    )
    (comp (ref "R117")
      (value "10K")
      (footprint "easyedapro:R0603")
      (libsource (lib "easyedapro") (part "Res"))
    )
    (comp (ref "R118")
      (value "10K")
      (footprint "easyedapro:R0603")
      (libsource (lib "easyedapro") (part "Res"))
    )
    (comp (ref "R119")
      (value "10K")
      (footprint "easyedapro:R0603")
      (libsource (lib "easyedapro") (part "Res"))
    )
    (comp (ref "R120")
      (value "10K")
      (footprint "easyedapro:R0603")
      (libsource (lib "easyedapro") (part "Res"))
    )
    (comp (ref "R121")
      (value "10K")
      (footprint "easyedapro:R0603")
      (libsource (lib "easyedapro") (part "Res"))
    )
    (comp (ref "R122")
      (value "10K")
      (footprint "easyedapro:R0603")
      (libsource (lib "easyedapro") (part "Res"))
    )
    (comp (ref "R123")
      (value "10K")
      (footprint "easyedapro:R0603")
      (libsource (lib "easyedapro") (part "Res"))
    )
    (comp (ref "R124")
      (value "10K")
      (footprint "easyedapro:R0603")
      (libsource (lib "easyedapro") (part "Res"))
    )
    (comp (ref "R125")
      (value "10K")
      (footprint "easyedapro:R0603")
      (libsource (lib "easyedapro") (part "Res"))
    )
    (comp (ref "R126")
      (value "10K")
      (footprint "easyedapro:R0603")
      (libsource (lib "easyedapro") (part "Res"))
    )
    (comp (ref "R127")
      (value "10K")
      (footprint "easyedapro:R0603")
      (libsource (lib "easyedapro") (part "Res"))
    )
    (comp (ref "R128")
      (value "10K")
      (footprint "easyedapro:R0603")
      (libsource (lib "easyedapro") (part "Res"))
    )
    (comp (ref "R129")
      (value "10K")
      (footprint "easyedapro:R0603")
      (libsource (lib "easyedapro") (part "Res"))
    )
    (comp (ref "R130")
      (value "10K")
      (footprint "easyedapro:R0603")
      (libsource (lib "easyedapro") (part "Res"))
    )
    (comp (ref "R131")
      (value "10K")
      (footprint "easyedapro:R0603")
      (libsource (lib "easyedapro") (part "Res"))
    )
    (comp (ref "R132")
      (value "10K")
      (footprint "easyedapro:R0603")
      (libsource (lib "easyedapro") (part "Res"))
    )
    (comp (ref "R133")
      (value "10K")
      (footprint "easyedapro:R0603")
      (libsource (lib "easyedapro") (part "Res"))
    )
    (comp (ref "R134")
      (value "10K")
      (footprint "easyedapro:R0603")
      (libsource (lib "easyedapro") (part "Res"))
    )
    (comp (ref "R135")
      (value "10K")
      (footprint "easyedapro:R0603")
      (libsource (lib "easyedapro") (part "Res"))
    )
    (comp (ref "R136")
      (value "10K")
      (footprint "easyedapro:R0603")
      (libsource (lib "easyedapro") (part "Res"))
    )
    (comp (ref "R137")
      (value "10K")
      (footprint "easyedapro:R0603")
      (libsource (lib "easyedapro") (part "Res"))
    )
    (comp (ref "R138")
      (value "10K")
      (footprint "easyedapro:R0603")
      (libsource (lib "easyedapro") (part "Res"))
    )
    (comp (ref "R139")
      (value "10K")
      (footprint "easyedapro:R0603")
      (libsource (lib "easyedapro") (part "Res"))
    )
    (comp (ref "R140")
      (value "10K")
      (footprint "easyedapro:R0603")
      (libsource (lib "easyedapro") (part "Res"))
    )
    (comp (ref "R141")
      (value "10K")
      (footprint "easyedapro:R0603")
      (libsource (lib "easyedapro") (part "Res"))
    )
    (comp (ref "R142")
      (value "10K")
      (footprint "easyedapro:R0603")
      (libsource (lib "easyedapro") (part "Res"))
    )
    (comp (ref "R143")
      (value "10K")
      (footprint "easyedapro:R0603")
      (libsource (lib "easyedapro") (part "Res"))
    )
    (comp (ref "R144")
      (value "10K")
      (footprint "easyedapro:R0603")
      (libsource (lib "easyedapro") (part "Res"))
    )
    (comp (ref "R145")
      (value "10K")
      (footprint "easyedapro:R0603")
      (libsource (lib "easyedapro") (part "Res"))
    )
    (comp (ref "R146")
      (value "10K")
      (footprint "easyedapro:R0603")
      (libsource (lib "easyedapro") (part "Res"))
    )
    (comp (ref "R147")
      (value "10K")
      (footprint "easyedapro:R0603")
      (libsource (lib "easyedapro") (part "Res"))
    )
    (comp (ref "R148")
      (value "10K")
      (footprint "easyedapro:R0603")
      (libsource (lib "easyedapro") (part "Res"))
    )
    (comp (ref "R149")
      (value "10K")
      (footprint "easyedapro:R0603")
      (libsource (lib "easyedapro") (part "Res"))
    )
    (comp (ref "R150")
      (value "10K")
      (footprint "easyedapro:R0603")
      (libsource (lib "easyedapro") (part "Res"))
    )
    (comp (ref "R151")
      (value "10K")
      (footprint "easyedapro:R0603")
      (libsource (lib "easyedapro") (part "Res"))
    )
    (comp (ref "R152")
      (value "10K")
      (footprint "easyedapro:R0603")
      (libsource (lib "easyedapro") (part "Res"))
    )
    (comp (ref "R153")
      (value "10K")
      (footprint "easyedapro:R0603")
      (libsource (lib "easyedapro") (part "Res"))
    )
    (comp (ref "R154")
      (value "10K")
      (footprint "easyedapro:R0603")
      (libsource (lib "easyedapro") (part "Res"))
    )
    (comp (ref "R155")
      (value "10K")
      (footprint "easyedapro:R0603")
      (libsource (lib "easyedapro") (part "Res"))
    )
    (comp (ref "R156")
      (value "10K")
      (footprint "easyedapro:R0603")
      (libsource (lib "easyedapro") (part "Res"))
    )
    (comp (ref "R157")
      (value "10K")
      (footprint "easyedapro:R0603")
      (libsource (lib "easyedapro") (part "Res"))
    )
    (comp (ref "R158")
      (value "10K")
      (footprint "easyedapro:R0603")
      (libsource (lib "easyedapro") (part "Res"))
    )
    (comp (ref "R159")
      (value "10K")
      (footprint "easyedapro:R0603")
      (libsource (lib "easyedapro") (part "Res"))
    )
    (comp (ref "R160")
      (value "10K")
      (footprint "easyedapro:R0603")
      (libsource (lib "easyedapro") (part "Res"))
    )
    (comp (ref "U21")
      (value "TL074CDR")
      (footprint "easyedapro:SOIC-14_L8.7-W3.9-P1.27-LS6.0-BL")
      (fields (field (name "Manufacturer") "TI(德州仪器)"))
      (libsource (lib "easyedapro") (part "TL074CDR"))
    )
    (comp (ref "U22")
      (value "TL074CDR")
      (footprint "easyedapro:SOIC-14_L8.7-W3.9-P1.27-LS6.0-BL")
      (fields (field (name "Manufacturer") "TI(德州仪器)"))
      (libsource (lib "easyedapro") (part "TL074CDR"))
    )
    (comp (ref "U23")
      (value "TL074CDR")
      (footprint "easyedapro:SOIC-14_L8.7-W3.9-P1.27-LS6.0-BL")
      (fields (field (name "Manufacturer") "TI(德州仪器)"))
      (libsource (lib "easyedapro") (part "TL074CDR"))
    )
    (comp (ref "U24")
      (value "TL074CDR")
      (footprint "easyedapro:SOIC-14_L8.7-W3.9-P1.27-LS6.0-BL")
      (fields (field (name "Manufacturer") "TI(德州仪器)"))
      (libsource (lib "easyedapro") (part "TL074CDR"))
    )
  )
  (nets
    (net (code "1") (name "+5V") (class "Default")
      (node (ref "R104") (pin "2") (pinfunction "2_2") (pintype "input"))
      (node (ref "R118") (pin "2") (pinfunction "2_2") (pintype "input"))
      (node (ref "R123") (pin "2") (pinfunction "2_2") (pintype "input"))
      (node (ref "R136") (pin "2") (pinfunction "2_2") (pintype "input"))
      (node (ref "R141") (pin "2") (pinfunction "2_2") (pintype "input"))
      (node (ref "R154") (pin "2") (pinfunction "2_2") (pintype "input"))
      (node (ref "R159") (pin "2") (pinfunction "2_2") (pintype "input"))
      (node (ref "R24") (pin "2") (pinfunction "2_2") (pintype "input"))
      (node (ref "R33") (pin "2") (pinfunction "2_2") (pintype "input"))
      (node (ref "R42") (pin "2") (pinfunction "2_2") (pintype "input"))
      (node (ref "R51") (pin "2") (pinfunction "2_2") (pintype "input"))
      (node (ref "R60") (pin "2") (pinfunction "2_2") (pintype "input"))
      (node (ref "R69") (pin "2") (pinfunction "2_2") (pintype "input"))
      (node (ref "R78") (pin "2") (pinfunction "2_2") (pintype "input"))
      (node (ref "R87") (pin "2") (pinfunction "2_2") (pintype "input"))
      (node (ref "R96") (pin "2") (pinfunction "2_2") (pintype "input"))
    )
    (net (code "2") (name "+12V") (class "Default")
      (node (ref "U17") (pin "4") (pinfunction "VCC+_4") (pintype "unspecified"))
      (node (ref "U18") (pin "4") (pinfunction "VCC+_4") (pintype "unspecified"))
      (node (ref "U19") (pin "4") (pinfunction "VCC+_4") (pintype "unspecified"))
      (node (ref "U20") (pin "4") (pinfunction "VCC+_4") (pintype "unspecified"))
      (node (ref "U21") (pin "4") (pinfunction "VCC+_4") (pintype "unspecified"))
      (node (ref "U22") (pin "4") (pinfunction "VCC+_4") (pintype "unspecified"))
      (node (ref "U23") (pin "4") (pinfunction "VCC+_4") (pintype "unspecified"))
      (node (ref "U24") (pin "4") (pinfunction "VCC+_4") (pintype "unspecified"))
    )
    (net (code "3") (name "-12V") (class "Default")
      (node (ref "U17") (pin "11") (pinfunction "VCC-_11") (pintype "unspecified"))
      (node (ref "U18") (pin "11") (pinfunction "VCC-_11") (pintype "unspecified"))
      (node (ref "U19") (pin "11") (pinfunction "VCC-_11") (pintype "unspecified"))
      (node (ref "U20") (pin "11") (pinfunction "VCC-_11") (pintype "unspecified"))
      (node (ref "U21") (pin "11") (pinfunction "VCC-_11") (pintype "unspecified"))
      (node (ref "U22") (pin "11") (pinfunction "VCC-_11") (pintype "unspecified"))
      (node (ref "U23") (pin "11") (pinfunction "VCC-_11") (pintype "unspecified"))
      (node (ref "U24") (pin "11") (pinfunction "VCC-_11") (pintype "unspecified"))
    )
    (net (code "4") (name "5V") (class "Default")
      (node (ref "R1") (pin "2") (pinfunction "2_2") (pintype "input"))
      (node (ref "R10") (pin "2") (pinfunction "2_2") (pintype "input"))
      (node (ref "R11") (pin "2") (pinfunction "2_2") (pintype "input"))
      (node (ref "R12") (pin "2") (pinfunction "2_2") (pintype "input"))
      (node (ref "R13") (pin "2") (pinfunction "2_2") (pintype "input"))
      (node (ref "R14") (pin "2") (pinfunction "2_2") (pintype "input"))
      (node (ref "R15") (pin "2") (pinfunction "2_2") (pintype "input"))
      (node (ref "R16") (pin "2") (pinfunction "2_2") (pintype "input"))
      (node (ref "R2") (pin "2") (pinfunction "2_2") (pintype "input"))
      (node (ref "R3") (pin "2") (pinfunction "2_2") (pintype "input"))
      (node (ref "R4") (pin "2") (pinfunction "2_2") (pintype "input"))
      (node (ref "R5") (pin "2") (pinfunction "2_2") (pintype "input"))
      (node (ref "R6") (pin "2") (pinfunction "2_2") (pintype "input"))
      (node (ref "R7") (pin "2") (pinfunction "2_2") (pintype "input"))
      (node (ref "R8") (pin "2") (pinfunction "2_2") (pintype "input"))
      (node (ref "R9") (pin "2") (pinfunction "2_2") (pintype "input"))
      (node (ref "U1") (pin "1") (pinfunction "CCW_1") (pintype "bidirectional"))
      (node (ref "U10") (pin "1") (pinfunction "CCW_1") (pintype "bidirectional"))
      (node (ref "U11") (pin "1") (pinfunction "CCW_1") (pintype "bidirectional"))
      (node (ref "U12") (pin "1") (pinfunction "CCW_1") (pintype "bidirectional"))
      (node (ref "U13") (pin "1") (pinfunction "CCW_1") (pintype "bidirectional"))
      (node (ref "U14") (pin "1") (pinfunction "CCW_1") (pintype "bidirectional"))
      (node (ref "U15") (pin "1") (pinfunction "CCW_1") (pintype "bidirectional"))
      (node (ref "U16") (pin "1") (pinfunction "CCW_1") (pintype "bidirectional"))
      (node (ref "U2") (pin "1") (pinfunction "CCW_1") (pintype "bidirectional"))
      (node (ref "U3") (pin "1") (pinfunction "CCW_1") (pintype "bidirectional"))
      (node (ref "U4") (pin "1") (pinfunction "CCW_1") (pintype "bidirectional"))
      (node (ref "U5") (pin "1") (pinfunction "CCW_1") (pintype "bidirectional"))
      (node (ref "U6") (pin "1") (pinfunction "CCW_1") (pintype "bidirectional"))
      (node (ref "U7") (pin "1") (pinfunction "CCW_1") (pintype "bidirectional"))
      (node (ref "U8") (pin "1") (pinfunction "CCW_1") (pintype "bidirectional"))
      (node (ref "U9") (pin "1") (pinfunction "CCW_1") (pintype "bidirectional"))
    )
    (net (code "5") (name "A0") (class "Default")
      (node (ref "U17") (pin "1") (pinfunction "OUT1_1") (pintype "output"))
      (node (ref "U17") (pin "2") (pinfunction "IN1-_2") (pintype "unspecified"))
      (node (ref "U18") (pin "1") (pinfunction "OUT1_1") (pintype "output"))
      (node (ref "U18") (pin "2") (pinfunction "IN1-_2") (pintype "unspecified"))
      (node (ref "U19") (pin "1") (pinfunction "OUT1_1") (pintype "output"))
      (node (ref "U19") (pin "2") (pinfunction "IN1-_2") (pintype "unspecified"))
      (node (ref "U20") (pin "1") (pinfunction "OUT1_1") (pintype "output"))
      (node (ref "U20") (pin "2") (pinfunction "IN1-_2") (pintype "unspecified"))
      (node (ref "U21") (pin "1") (pinfunction "OUT1_1") (pintype "output"))
      (node (ref "U21") (pin "2") (pinfunction "IN1-_2") (pintype "unspecified"))
      (node (ref "U22") (pin "1") (pinfunction "OUT1_1") (pintype "output"))
      (node (ref "U22") (pin "2") (pinfunction "IN1-_2") (pintype "unspecified"))
      (node (ref "U23") (pin "1") (pinfunction "OUT1_1") (pintype "output"))
      (node (ref "U23") (pin "2") (pinfunction "IN1-_2") (pintype "unspecified"))
      (node (ref "U24") (pin "1") (pinfunction "OUT1_1") (pintype "output"))
      (node (ref "U24") (pin "2") (pinfunction "IN1-_2") (pintype "unspecified"))
    )
    (net (code "6") (name "A1") (class "Default")
      (node (ref "U17") (pin "8") (pinfunction "OUT3_8") (pintype "output"))
      (node (ref "U17") (pin "9") (pinfunction "IN3-_9") (pintype "unspecified"))
      (node (ref "U18") (pin "8") (pinfunction "OUT3_8") (pintype "output"))
      (node (ref "U18") (pin "9") (pinfunction "IN3-_9") (pintype "unspecified"))
      (node (ref "U19") (pin "8") (pinfunction "OUT3_8") (pintype "output"))
      (node (ref "U19") (pin "9") (pinfunction "IN3-_9") (pintype "unspecified"))
      (node (ref "U20") (pin "8") (pinfunction "OUT3_8") (pintype "output"))
      (node (ref "U20") (pin "9") (pinfunction "IN3-_9") (pintype "unspecified"))
      (node (ref "U21") (pin "8") (pinfunction "OUT3_8") (pintype "output"))
      (node (ref "U21") (pin "9") (pinfunction "IN3-_9") (pintype "unspecified"))
      (node (ref "U22") (pin "8") (pinfunction "OUT3_8") (pintype "output"))
      (node (ref "U22") (pin "9") (pinfunction "IN3-_9") (pintype "unspecified"))
      (node (ref "U23") (pin "8") (pinfunction "OUT3_8") (pintype "output"))
      (node (ref "U23") (pin "9") (pinfunction "IN3-_9") (pintype "unspecified"))
      (node (ref "U24") (pin "8") (pinfunction "OUT3_8") (pintype "output"))
      (node (ref "U24") (pin "9") (pinfunction "IN3-_9") (pintype "unspecified"))
    )
    (net (code "7") (name "GND") (class "Default")
      (node (ref "R100") (pin "1") (pinfunction "1_1") (pintype "input"))
      (node (ref "R105") (pin "1") (pinfunction "1_1") (pintype "input"))
      (node (ref "R107") (pin "1") (pinfunction "1_1") (pintype "input"))
      (node (ref "R111") (pin "1") (pinfunction "1_1") (pintype "input"))
      (node (ref "R113") (pin "1") (pinfunction "1_1") (pintype "input"))
      (node (ref "R114") (pin "1") (pinfunction "1_1") (pintype "input"))
      (node (ref "R116") (pin "1") (pinfunction "1_1") (pintype "input"))
      (node (ref "R121") (pin "1") (pinfunction "1_1") (pintype "input"))
      (node (ref "R125") (pin "1") (pinfunction "1_1") (pintype "input"))
      (node (ref "R129") (pin "1") (pinfunction "1_1") (pintype "input"))
      (node (ref "R131") (pin "1") (pinfunction "1_1") (pintype "input"))
      (node (ref "R132") (pin "1") (pinfunction "1_1") (pintype "input"))
      (node (ref "R134") (pin "1") (pinfunction "1_1") (pintype "input"))
      (node (ref "R139") (pin "1") (pinfunction "1_1") (pintype "input"))
      (node (ref "R143") (pin "1") (pinfunction "1_1") (pintype "input"))
      (node (ref "R147") (pin "1") (pinfunction "1_1") (pintype "input"))
      (node (ref "R149") (pin "1") (pinfunction "1_1") (pintype "input"))
      (node (ref "R150") (pin "1") (pinfunction "1_1") (pintype "input"))
      (node (ref "R152") (pin "1") (pinfunction "1_1") (pintype "input"))
      (node (ref "R157") (pin "1") (pinfunction "1_1") (pintype "input"))
      (node (ref "R18") (pin "1") (pinfunction "1_1") (pintype "input"))
      (node (ref "R22") (pin "1") (pinfunction "1_1") (pintype "input"))
      (node (ref "R25") (pin "1") (pinfunction "1_1") (pintype "input"))
      (node (ref "R27") (pin "1") (pinfunction "1_1") (pintype "input"))
      (node (ref "R31") (pin "1") (pinfunction "1_1") (pintype "input"))
      (node (ref "R34") (pin "1") (pinfunction "1_1") (pintype "input"))
      (node (ref "R36") (pin "1") (pinfunction "1_1") (pintype "input"))
      (node (ref "R40") (pin "1") (pinfunction "1_1") (pintype "input"))
      (node (ref "R43") (pin "1") (pinfunction "1_1") (pintype "input"))
      (node (ref "R45") (pin "1") (pinfunction "1_1") (pintype "input"))
      (node (ref "R49") (pin "1") (pinfunction "1_1") (pintype "input"))
      (node (ref "R52") (pin "1") (pinfunction "1_1") (pintype "input"))
      (node (ref "R54") (pin "1") (pinfunction "1_1") (pintype "input"))
      (node (ref "R58") (pin "1") (pinfunction "1_1") (pintype "input"))
      (node (ref "R61") (pin "1") (pinfunction "1_1") (pintype "input"))
      (node (ref "R63") (pin "1") (pinfunction "1_1") (pintype "input"))
      (node (ref "R67") (pin "1") (pinfunction "1_1") (pintype "input"))
      (node (ref "R70") (pin "1") (pinfunction "1_1") (pintype "input"))
      (node (ref "R72") (pin "1") (pinfunction "1_1") (pintype "input"))
      (node (ref "R76") (pin "1") (pinfunction "1_1") (pintype "input"))
      (node (ref "R79") (pin "1") (pinfunction "1_1") (pintype "input"))
      (node (ref "R81") (pin "1") (pinfunction "1_1") (pintype "input"))
      (node (ref "R85") (pin "1") (pinfunction "1_1") (pintype "input"))
      (node (ref "R88") (pin "1") (pinfunction "1_1") (pintype "input"))
      (node (ref "R90") (pin "1") (pinfunction "1_1") (pintype "input"))
      (node (ref "R94") (pin "1") (pinfunction "1_1") (pintype "input"))
      (node (ref "R97") (pin "1") (pinfunction "1_1") (pintype "input"))
      (node (ref "R98") (pin "1") (pinfunction "1_1") (pintype "input"))
      (node (ref "U1") (pin "3") (pinfunction "CW_3") (pintype "bidirectional"))
      (node (ref "U1") (pin "E1") (pinfunction "E_(-)_E1") (pintype "bidirectional"))
      (node (ref "U10") (pin "3") (pinfunction "CW_3") (pintype "bidirectional"))
      (node (ref "U10") (pin "E1") (pinfunction "E_(-)_E1") (pintype "bidirectional"))
      (node (ref "U11") (pin "3") (pinfunction "CW_3") (pintype "bidirectional"))
      (node (ref "U11") (pin "E1") (pinfunction "E_(-)_E1") (pintype "bidirectional"))
      (node (ref "U12") (pin "3") (pinfunction "CW_3") (pintype "bidirectional"))
      (node (ref "U12") (pin "E1") (pinfunction "E_(-)_E1") (pintype "bidirectional"))
      (node (ref "U13") (pin "3") (pinfunction "CW_3") (pintype "bidirectional"))
      (node (ref "U13") (pin "E1") (pinfunction "E_(-)_E1") (pintype "bidirectional"))
      (node (ref "U14") (pin "3") (pinfunction "CW_3") (pintype "bidirectional"))
      (node (ref "U14") (pin "E1") (pinfunction "E_(-)_E1") (pintype "bidirectional"))
      (node (ref "U15") (pin "3") (pinfunction "CW_3") (pintype "bidirectional"))
      (node (ref "U15") (pin "E1") (pinfunction "E_(-)_E1") (pintype "bidirectional"))
      (node (ref "U16") (pin "3") (pinfunction "CW_3") (pintype "bidirectional"))
      (node (ref "U16") (pin "E1") (pinfunction "E_(-)_E1") (pintype "bidirectional"))
      (node (ref "U2") (pin "3") (pinfunction "CW_3") (pintype "bidirectional"))
      (node (ref "U2") (pin "E1") (pinfunction "E_(-)_E1") (pintype "bidirectional"))
      (node (ref "U3") (pin "3") (pinfunction "CW_3") (pintype "bidirectional"))
      (node (ref "U3") (pin "E1") (pinfunction "E_(-)_E1") (pintype "bidirectional"))
      (node (ref "U4") (pin "3") (pinfunction "CW_3") (pintype "bidirectional"))
      (node (ref "U4") (pin "E1") (pinfunction "E_(-)_E1") (pintype "bidirectional"))
      (node (ref "U5") (pin "3") (pinfunction "CW_3") (pintype "bidirectional"))
      (node (ref "U5") (pin "E1") (pinfunction "E_(-)_E1") (pintype "bidirectional"))
      (node (ref "U6") (pin "3") (pinfunction "CW_3") (pintype "bidirectional"))
      (node (ref "U6") (pin "E1") (pinfunction "E_(-)_E1") (pintype "bidirectional"))
      (node (ref "U7") (pin "3") (pinfunction "CW_3") (pintype "bidirectional"))
      (node (ref "U7") (pin "E1") (pinfunction "E_(-)_E1") (pintype "bidirectional"))
      (node (ref "U8") (pin "3") (pinfunction "CW_3") (pintype "bidirectional"))
      (node (ref "U8") (pin "E1") (pinfunction "E_(-)_E1") (pintype "bidirectional"))
      (node (ref "U9") (pin "3") (pinfunction "CW_3") (pintype "bidirectional"))
      (node (ref "U9") (pin "E1") (pinfunction "E_(-)_E1") (pintype "bidirectional"))
    )
    (net (code "8") (name "J0") (class "Default")
      (node (ref "R115") (pin "2") (pinfunction "2_2") (pintype "input"))
      (node (ref "R133") (pin "2") (pinfunction "2_2") (pintype "input"))
      (node (ref "R151") (pin "2") (pinfunction "2_2") (pintype "input"))
      (node (ref "R23") (pin "2") (pinfunction "2_2") (pintype "input"))
      (node (ref "R41") (pin "2") (pinfunction "2_2") (pintype "input"))
      (node (ref "R59") (pin "2") (pinfunction "2_2") (pintype "input"))
      (node (ref "R77") (pin "2") (pinfunction "2_2") (pintype "input"))
      (node (ref "R95") (pin "2") (pinfunction "2_2") (pintype "input"))
    )
    (net (code "9") (name "J1") (class "Default")
      (node (ref "R106") (pin "2") (pinfunction "2_2") (pintype "input"))
      (node (ref "R110") (pin "2") (pinfunction "2_2") (pintype "input"))
      (node (ref "R128") (pin "2") (pinfunction "2_2") (pintype "input"))
      (node (ref "R146") (pin "2") (pinfunction "2_2") (pintype "input"))
      (node (ref "R32") (pin "2") (pinfunction "2_2") (pintype "input"))
      (node (ref "R50") (pin "2") (pinfunction "2_2") (pintype "input"))
      (node (ref "R68") (pin "2") (pinfunction "2_2") (pintype "input"))
      (node (ref "R86") (pin "2") (pinfunction "2_2") (pintype "input"))
    )
    (net (code "10") (name "Net-(R20-Pad1)") (class "Default")
      (node (ref "R20") (pin "1") (pinfunction "1_1") (pintype "input"))
      (node (ref "R24") (pin "1") (pinfunction "1_1") (pintype "input"))
      (node (ref "R25") (pin "2") (pinfunction "2_2") (pintype "input"))
    )
    (net (code "11") (name "Net-(R29-Pad1)") (class "Default")
      (node (ref "R29") (pin "1") (pinfunction "1_1") (pintype "input"))
      (node (ref "R33") (pin "1") (pinfunction "1_1") (pintype "input"))
      (node (ref "R34") (pin "2") (pinfunction "2_2") (pintype "input"))
    )
    (net (code "12") (name "Net-(R38-Pad1)") (class "Default")
      (node (ref "R38") (pin "1") (pinfunction "1_1") (pintype "input"))
      (node (ref "R42") (pin "1") (pinfunction "1_1") (pintype "input"))
      (node (ref "R43") (pin "2") (pinfunction "2_2") (pintype "input"))
    )
    (net (code "13") (name "Net-(R47-Pad1)") (class "Default")
      (node (ref "R47") (pin "1") (pinfunction "1_1") (pintype "input"))
      (node (ref "R51") (pin "1") (pinfunction "1_1") (pintype "input"))
      (node (ref "R52") (pin "2") (pinfunction "2_2") (pintype "input"))
    )
    (net (code "14") (name "Net-(R56-Pad1)") (class "Default")
      (node (ref "R56") (pin "1") (pinfunction "1_1") (pintype "input"))
      (node (ref "R60") (pin "1") (pinfunction "1_1") (pintype "input"))
      (node (ref "R61") (pin "2") (pinfunction "2_2") (pintype "input"))
    )
    (net (code "15") (name "Net-(R65-Pad1)") (class "Default")
      (node (ref "R65") (pin "1") (pinfunction "1_1") (pintype "input"))
      (node (ref "R69") (pin "1") (pinfunction "1_1") (pintype "input"))
      (node (ref "R70") (pin "2") (pinfunction "2_2") (pintype "input"))
    )
    (net (code "16") (name "Net-(R74-Pad1)") (class "Default")
      (node (ref "R74") (pin "1") (pinfunction "1_1") (pintype "input"))
      (node (ref "R78") (pin "1") (pinfunction "1_1") (pintype "input"))
      (node (ref "R79") (pin "2") (pinfunction "2_2") (pintype "input"))
    )
    (net (code "17") (name "Net-(R83-Pad1)") (class "Default")
      (node (ref "R83") (pin "1") (pinfunction "1_1") (pintype "input"))
      (node (ref "R87") (pin "1") (pinfunction "1_1") (pintype "input"))
      (node (ref "R88") (pin "2") (pinfunction "2_2") (pintype "input"))
    )
    (net (code "18") (name "Net-(R92-Pad1)") (class "Default")
      (node (ref "R92") (pin "1") (pinfunction "1_1") (pintype "input"))
      (node (ref "R96") (pin "1") (pinfunction "1_1") (pintype "input"))
      (node (ref "R97") (pin "2") (pinfunction "2_2") (pintype "input"))
    )
    (net (code "19") (name "Net-(R103-Pad1)") (class "Default")
      (node (ref "R103") (pin "1") (pinfunction "1_1") (pintype "input"))
      (node (ref "R104") (pin "1") (pinfunction "1_1") (pintype "input"))
      (node (ref "R105") (pin "2") (pinfunction "2_2") (pintype "input"))
    )
    (net (code "20") (name "Net-(R116-Pad2)") (class "Default")
      (node (ref "R116") (pin "2") (pinfunction "2_2") (pintype "input"))
      (node (ref "R117") (pin "1") (pinfunction "1_1") (pintype "input"))
      (node (ref "R118") (pin "1") (pinfunction "1_1") (pintype "input"))
    )
    (net (code "21") (name "Net-(R120-Pad1)") (class "Default")
      (node (ref "R120") (pin "1") (pinfunction "1_1") (pintype "input"))
      (node (ref "R121") (pin "2") (pinfunction "2_2") (pintype "input"))
      (node (ref "R123") (pin "1") (pinfunction "1_1") (pintype "input"))
    )
    (net (code "22") (name "Net-(R134-Pad2)") (class "Default")
      (node (ref "R134") (pin "2") (pinfunction "2_2") (pintype "input"))
      (node (ref "R135") (pin "1") (pinfunction "1_1") (pintype "input"))
      (node (ref "R136") (pin "1") (pinfunction "1_1") (pintype "input"))
    )
    (net (code "23") (name "Net-(R138-Pad1)") (class "Default")
      (node (ref "R138") (pin "1") (pinfunction "1_1") (pintype "input"))
      (node (ref "R139") (pin "2") (pinfunction "2_2") (pintype "input"))
      (node (ref "R141") (pin "1") (pinfunction "1_1") (pintype "input"))
    )
    (net (code "24") (name "Net-(R152-Pad2)") (class "Default")
      (node (ref "R152") (pin "2") (pinfunction "2_2") (pintype "input"))
      (node (ref "R153") (pin "1") (pinfunction "1_1") (pintype "input"))
      (node (ref "R154") (pin "1") (pinfunction "1_1") (pintype "input"))
    )
    (net (code "25") (name "Net-(R156-Pad1)") (class "Default")
      (node (ref "R156") (pin "1") (pinfunction "1_1") (pintype "input"))
      (node (ref "R157") (pin "2") (pinfunction "2_2") (pintype "input"))
      (node (ref "R159") (pin "1") (pinfunction "1_1") (pintype "input"))
    )
    (net (code "26") (name "Net-(U1-B_(+))") (class "Default")
      (node (ref "R1") (pin "1") (pinfunction "1_1") (pintype "input"))
      (node (ref "U1") (pin "B1") (pinfunction "B_(+)_B1") (pintype "bidirectional"))
    )
    (net (code "27") (name "Net-(U2-B_(+))") (class "Default")
      (node (ref "R2") (pin "1") (pinfunction "1_1") (pintype "input"))
      (node (ref "U2") (pin "B1") (pinfunction "B_(+)_B1") (pintype "bidirectional"))
    )
    (net (code "28") (name "Net-(U3-B_(+))") (class "Default")
      (node (ref "R3") (pin "1") (pinfunction "1_1") (pintype "input"))
      (node (ref "U3") (pin "B1") (pinfunction "B_(+)_B1") (pintype "bidirectional"))
    )
    (net (code "29") (name "Net-(U4-B_(+))") (class "Default")
      (node (ref "R4") (pin "1") (pinfunction "1_1") (pintype "input"))
      (node (ref "U4") (pin "B1") (pinfunction "B_(+)_B1") (pintype "bidirectional"))
    )
    (net (code "30") (name "Net-(U5-B_(+))") (class "Default")
      (node (ref "R5") (pin "1") (pinfunction "1_1") (pintype "input"))
      (node (ref "U5") (pin "B1") (pinfunction "B_(+)_B1") (pintype "bidirectional"))
    )
    (net (code "31") (name "Net-(U6-B_(+))") (class "Default")
      (node (ref "R6") (pin "1") (pinfunction "1_1") (pintype "input"))
      (node (ref "U6") (pin "B1") (pinfunction "B_(+)_B1") (pintype "bidirectional"))
    )
    (net (code "32") (name "Net-(U7-B_(+))") (class "Default")
      (node (ref "R7") (pin "1") (pinfunction "1_1") (pintype "input"))
      (node (ref "U7") (pin "B1") (pinfunction "B_(+)_B1") (pintype "bidirectional"))
    )
    (net (code "33") (name "Net-(U8-B_(+))") (class "Default")
      (node (ref "R8") (pin "1") (pinfunction "1_1") (pintype "input"))
      (node (ref "U8") (pin "B1") (pinfunction "B_(+)_B1") (pintype "bidirectional"))
    )
    (net (code "34") (name "Net-(U9-B_(+))") (class "Default")
      (node (ref "R9") (pin "1") (pinfunction "1_1") (pintype "input"))
      (node (ref "U9") (pin "B1") (pinfunction "B_(+)_B1") (pintype "bidirectional"))
    )
    (net (code "35") (name "Net-(U10-B_(+))") (class "Default")
      (node (ref "R10") (pin "1") (pinfunction "1_1") (pintype "input"))
      (node (ref "U10") (pin "B1") (pinfunction "B_(+)_B1") (pintype "bidirectional"))
    )
    (net (code "36") (name "Net-(U11-B_(+))") (class "Default")
      (node (ref "R11") (pin "1") (pinfunction "1_1") (pintype "input"))
      (node (ref "U11") (pin "B1") (pinfunction "B_(+)_B1") (pintype "bidirectional"))
    )
    (net (code "37") (name "Net-(U12-B_(+))") (class "Default")
      (node (ref "R12") (pin "1") (pinfunction "1_1") (pintype "input"))
      (node (ref "U12") (pin "B1") (pinfunction "B_(+)_B1") (pintype "bidirectional"))
    )
    (net (code "38") (name "Net-(U13-B_(+))") (class "Default")
      (node (ref "R13") (pin "1") (pinfunction "1_1") (pintype "input"))
      (node (ref "U13") (pin "B1") (pinfunction "B_(+)_B1") (pintype "bidirectional"))
    )
    (net (code "39") (name "Net-(U14-B_(+))") (class "Default")
      (node (ref "R14") (pin "1") (pinfunction "1_1") (pintype "input"))
      (node (ref "U14") (pin "B1") (pinfunction "B_(+)_B1") (pintype "bidirectional"))
    )
    (net (code "40") (name "Net-(U15-B_(+))") (class "Default")
      (node (ref "R15") (pin "1") (pinfunction "1_1") (pintype "input"))
      (node (ref "U15") (pin "B1") (pinfunction "B_(+)_B1") (pintype "bidirectional"))
    )
    (net (code "41") (name "Net-(U16-B_(+))") (class "Default")
      (node (ref "R16") (pin "1") (pinfunction "1_1") (pintype "input"))
      (node (ref "U16") (pin "B1") (pinfunction "B_(+)_B1") (pintype "bidirectional"))
    )
    (net (code "42") (name "Net-(U17A-IN1+)") (class "Default")
      (node (ref "R17") (pin "2") (pinfunction "2_2") (pintype "input"))
      (node (ref "R18") (pin "2") (pinfunction "2_2") (pintype "input"))
      (node (ref "U17") (pin "3") (pinfunction "IN1+_3") (pintype "unspecified"))
    )
    (net (code "43") (name "Net-(U17B-IN2+)") (class "Default")
      (node (ref "R19") (pin "2") (pinfunction "2_2") (pintype "input"))
      (node (ref "U17") (pin "5") (pinfunction "IN2+_5") (pintype "unspecified"))
    )
    (net (code "44") (name "Net-(U17B-IN2-)") (class "Default")
      (node (ref "R20") (pin "2") (pinfunction "2_2") (pintype "input"))
      (node (ref "R21") (pin "1") (pinfunction "1_1") (pintype "input"))
      (node (ref "U17") (pin "6") (pinfunction "IN2-_6") (pintype "unspecified"))
    )
    (net (code "45") (name "Net-(U17B-OUT2)") (class "Default")
      (node (ref "R21") (pin "2") (pinfunction "2_2") (pintype "input"))
      (node (ref "R22") (pin "2") (pinfunction "2_2") (pintype "input"))
      (node (ref "R23") (pin "1") (pinfunction "1_1") (pintype "input"))
      (node (ref "U17") (pin "7") (pinfunction "OUT2_7") (pintype "output"))
    )
    (net (code "46") (name "Net-(U17C-IN3+)") (class "Default")
      (node (ref "R26") (pin "2") (pinfunction "2_2") (pintype "input"))
      (node (ref "R27") (pin "2") (pinfunction "2_2") (pintype "input"))
      (node (ref "U17") (pin "10") (pinfunction "IN3+_10") (pintype "unspecified"))
    )
    (net (code "47") (name "Net-(U17D-IN4+)") (class "Default")
      (node (ref "R28") (pin "2") (pinfunction "2_2") (pintype "input"))
      (node (ref "U17") (pin "12") (pinfunction "IN4+_12") (pintype "unspecified"))
    )
    (net (code "48") (name "Net-(U17D-IN4-)") (class "Default")
      (node (ref "R29") (pin "2") (pinfunction "2_2") (pintype "input"))
      (node (ref "R30") (pin "1") (pinfunction "1_1") (pintype "input"))
      (node (ref "U17") (pin "13") (pinfunction "IN4-_13") (pintype "unspecified"))
    )
    (net (code "49") (name "Net-(U17D-OUT4)") (class "Default")
      (node (ref "R30") (pin "2") (pinfunction "2_2") (pintype "input"))
      (node (ref "R31") (pin "2") (pinfunction "2_2") (pintype "input"))
      (node (ref "R32") (pin "1") (pinfunction "1_1") (pintype "input"))
      (node (ref "U17") (pin "14") (pinfunction "OUT4_14") (pintype "output"))
    )
    (net (code "50") (name "Net-(U18A-IN1+)") (class "Default")
      (node (ref "R35") (pin "2") (pinfunction "2_2") (pintype "input"))
      (node (ref "R36") (pin "2") (pinfunction "2_2") (pintype "input"))
      (node (ref "U18") (pin "3") (pinfunction "IN1+_3") (pintype "unspecified"))
    )
    (net (code "51") (name "Net-(U18B-IN2+)") (class "Default")
      (node (ref "R37") (pin "2") (pinfunction "2_2") (pintype "input"))
      (node (ref "U18") (pin "5") (pinfunction "IN2+_5") (pintype "unspecified"))
    )
    (net (code "52") (name "Net-(U18B-IN2-)") (class "Default")
      (node (ref "R38") (pin "2") (pinfunction "2_2") (pintype "input"))
      (node (ref "R39") (pin "1") (pinfunction "1_1") (pintype "input"))
      (node (ref "U18") (pin "6") (pinfunction "IN2-_6") (pintype "unspecified"))
    )
    (net (code "53") (name "Net-(U18B-OUT2)") (class "Default")
      (node (ref "R39") (pin "2") (pinfunction "2_2") (pintype "input"))
      (node (ref "R40") (pin "2") (pinfunction "2_2") (pintype "input"))
      (node (ref "R41") (pin "1") (pinfunction "1_1") (pintype "input"))
      (node (ref "U18") (pin "7") (pinfunction "OUT2_7") (pintype "output"))
    )
    (net (code "54") (name "Net-(U18C-IN3+)") (class "Default")
      (node (ref "R44") (pin "2") (pinfunction "2_2") (pintype "input"))
      (node (ref "R45") (pin "2") (pinfunction "2_2") (pintype "input"))
      (node (ref "U18") (pin "10") (pinfunction "IN3+_10") (pintype "unspecified"))
    )
    (net (code "55") (name "Net-(U18D-IN4+)") (class "Default")
      (node (ref "R46") (pin "2") (pinfunction "2_2") (pintype "input"))
      (node (ref "U18") (pin "12") (pinfunction "IN4+_12") (pintype "unspecified"))
    )
    (net (code "56") (name "Net-(U18D-IN4-)") (class "Default")
      (node (ref "R47") (pin "2") (pinfunction "2_2") (pintype "input"))
      (node (ref "R48") (pin "1") (pinfunction "1_1") (pintype "input"))
      (node (ref "U18") (pin "13") (pinfunction "IN4-_13") (pintype "unspecified"))
    )
    (net (code "57") (name "Net-(U18D-OUT4)") (class "Default")
      (node (ref "R48") (pin "2") (pinfunction "2_2") (pintype "input"))
      (node (ref "R49") (pin "2") (pinfunction "2_2") (pintype "input"))
      (node (ref "R50") (pin "1") (pinfunction "1_1") (pintype "input"))
      (node (ref "U18") (pin "14") (pinfunction "OUT4_14") (pintype "output"))
    )
    (net (code "58") (name "Net-(U19A-IN1+)") (class "Default")
      (node (ref "R53") (pin "2") (pinfunction "2_2") (pintype "input"))
      (node (ref "R54") (pin "2") (pinfunction "2_2") (pintype "input"))
      (node (ref "U19") (pin "3") (pinfunction "IN1+_3") (pintype "unspecified"))
    )
    (net (code "59") (name "Net-(U19B-IN2+)") (class "Default")
      (node (ref "R55") (pin "2") (pinfunction "2_2") (pintype "input"))
      (node (ref "U19") (pin "5") (pinfunction "IN2+_5") (pintype "unspecified"))
    )
    (net (code "60") (name "Net-(U19B-IN2-)") (class "Default")
      (node (ref "R56") (pin "2") (pinfunction "2_2") (pintype "input"))
      (node (ref "R57") (pin "1") (pinfunction "1_1") (pintype "input"))
      (node (ref "U19") (pin "6") (pinfunction "IN2-_6") (pintype "unspecified"))
    )
    (net (code "61") (name "Net-(U19B-OUT2)") (class "Default")
      (node (ref "R57") (pin "2") (pinfunction "2_2") (pintype "input"))
      (node (ref "R58") (pin "2") (pinfunction "2_2") (pintype "input"))
      (node (ref "R59") (pin "1") (pinfunction "1_1") (pintype "input"))
      (node (ref "U19") (pin "7") (pinfunction "OUT2_7") (pintype "output"))
    )
    (net (code "62") (name "Net-(U19C-IN3+)") (class "Default")
      (node (ref "R62") (pin "2") (pinfunction "2_2") (pintype "input"))
      (node (ref "R63") (pin "2") (pinfunction "2_2") (pintype "input"))
      (node (ref "U19") (pin "10") (pinfunction "IN3+_10") (pintype "unspecified"))
    )
    (net (code "63") (name "Net-(U19D-IN4+)") (class "Default")
      (node (ref "R64") (pin "2") (pinfunction "2_2") (pintype "input"))
      (node (ref "U19") (pin "12") (pinfunction "IN4+_12") (pintype "unspecified"))
    )
    (net (code "64") (name "Net-(U19D-IN4-)") (class "Default")
      (node (ref "R65") (pin "2") (pinfunction "2_2") (pintype "input"))
      (node (ref "R66") (pin "1") (pinfunction "1_1") (pintype "input"))
      (node (ref "U19") (pin "13") (pinfunction "IN4-_13") (pintype "unspecified"))
    )
    (net (code "65") (name "Net-(U19D-OUT4)") (class "Default")
      (node (ref "R66") (pin "2") (pinfunction "2_2") (pintype "input"))
      (node (ref "R67") (pin "2") (pinfunction "2_2") (pintype "input"))
      (node (ref "R68") (pin "1") (pinfunction "1_1") (pintype "input"))
      (node (ref "U19") (pin "14") (pinfunction "OUT4_14") (pintype "output"))
    )
    (net (code "66") (name "Net-(U20A-IN1+)") (class "Default")
      (node (ref "R71") (pin "2") (pinfunction "2_2") (pintype "input"))
      (node (ref "R72") (pin "2") (pinfunction "2_2") (pintype "input"))
      (node (ref "U20") (pin "3") (pinfunction "IN1+_3") (pintype "unspecified"))
    )
    (net (code "67") (name "Net-(U20B-IN2+)") (class "Default")
      (node (ref "R73") (pin "2") (pinfunction "2_2") (pintype "input"))
      (node (ref "U20") (pin "5") (pinfunction "IN2+_5") (pintype "unspecified"))
    )
    (net (code "68") (name "Net-(U20B-IN2-)") (class "Default")
      (node (ref "R74") (pin "2") (pinfunction "2_2") (pintype "input"))
      (node (ref "R75") (pin "1") (pinfunction "1_1") (pintype "input"))
      (node (ref "U20") (pin "6") (pinfunction "IN2-_6") (pintype "unspecified"))
    )
    (net (code "69") (name "Net-(U20B-OUT2)") (class "Default")
      (node (ref "R75") (pin "2") (pinfunction "2_2") (pintype "input"))
      (node (ref "R76") (pin "2") (pinfunction "2_2") (pintype "input"))
      (node (ref "R77") (pin "1") (pinfunction "1_1") (pintype "input"))
      (node (ref "U20") (pin "7") (pinfunction "OUT2_7") (pintype "output"))
    )
    (net (code "70") (name "Net-(U20C-IN3+)") (class "Default")
      (node (ref "R80") (pin "2") (pinfunction "2_2") (pintype "input"))
      (node (ref "R81") (pin "2") (pinfunction "2_2") (pintype "input"))
      (node (ref "U20") (pin "10") (pinfunction "IN3+_10") (pintype "unspecified"))
    )
    (net (code "71") (name "Net-(U20D-IN4+)") (class "Default")
      (node (ref "R82") (pin "2") (pinfunction "2_2") (pintype "input"))
      (node (ref "U20") (pin "12") (pinfunction "IN4+_12") (pintype "unspecified"))
    )
    (net (code "72") (name "Net-(U20D-IN4-)") (class "Default")
      (node (ref "R83") (pin "2") (pinfunction "2_2") (pintype "input"))
      (node (ref "R84") (pin "1") (pinfunction "1_1") (pintype "input"))
      (node (ref "U20") (pin "13") (pinfunction "IN4-_13") (pintype "unspecified"))
    )
    (net (code "73") (name "Net-(U20D-OUT4)") (class "Default")
      (node (ref "R84") (pin "2") (pinfunction "2_2") (pintype "input"))
      (node (ref "R85") (pin "2") (pinfunction "2_2") (pintype "input"))
      (node (ref "R86") (pin "1") (pinfunction "1_1") (pintype "input"))
      (node (ref "U20") (pin "14") (pinfunction "OUT4_14") (pintype "output"))
    )
    (net (code "74") (name "Net-(U21A-IN1+)") (class "Default")
      (node (ref "R89") (pin "2") (pinfunction "2_2") (pintype "input"))
      (node (ref "R90") (pin "2") (pinfunction "2_2") (pintype "input"))
      (node (ref "U21") (pin "3") (pinfunction "IN1+_3") (pintype "unspecified"))
    )
    (net (code "75") (name "Net-(U21B-IN2+)") (class "Default")
      (node (ref "R91") (pin "2") (pinfunction "2_2") (pintype "input"))
      (node (ref "U21") (pin "5") (pinfunction "IN2+_5") (pintype "unspecified"))
    )
    (net (code "76") (name "Net-(U21B-IN2-)") (class "Default")
      (node (ref "R92") (pin "2") (pinfunction "2_2") (pintype "input"))
      (node (ref "R93") (pin "1") (pinfunction "1_1") (pintype "input"))
      (node (ref "U21") (pin "6") (pinfunction "IN2-_6") (pintype "unspecified"))
    )
    (net (code "77") (name "Net-(U21B-OUT2)") (class "Default")
      (node (ref "R93") (pin "2") (pinfunction "2_2") (pintype "input"))
      (node (ref "R94") (pin "2") (pinfunction "2_2") (pintype "input"))
      (node (ref "R95") (pin "1") (pinfunction "1_1") (pintype "input"))
      (node (ref "U21") (pin "7") (pinfunction "OUT2_7") (pintype "output"))
    )
    (net (code "78") (name "Net-(U21C-IN3+)") (class "Default")
      (node (ref "R98") (pin "2") (pinfunction "2_2") (pintype "input"))
      (node (ref "R99") (pin "2") (pinfunction "2_2") (pintype "input"))
      (node (ref "U21") (pin "10") (pinfunction "IN3+_10") (pintype "unspecified"))
    )
    (net (code "79") (name "Net-(U21D-IN4+)") (class "Default")
      (node (ref "R102") (pin "2") (pinfunction "2_2") (pintype "input"))
      (node (ref "U21") (pin "12") (pinfunction "IN4+_12") (pintype "unspecified"))
    )
    (net (code "80") (name "Net-(U21D-IN4-)") (class "Default")
      (node (ref "R101") (pin "1") (pinfunction "1_1") (pintype "input"))
      (node (ref "R103") (pin "2") (pinfunction "2_2") (pintype "input"))
      (node (ref "U21") (pin "13") (pinfunction "IN4-_13") (pintype "unspecified"))
    )
    (net (code "81") (name "Net-(U21D-OUT4)") (class "Default")
      (node (ref "R100") (pin "2") (pinfunction "2_2") (pintype "input"))
      (node (ref "R101") (pin "2") (pinfunction "2_2") (pintype "input"))
      (node (ref "R106") (pin "1") (pinfunction "1_1") (pintype "input"))
      (node (ref "U21") (pin "14") (pinfunction "OUT4_14") (pintype "output"))
    )
    (net (code "82") (name "Net-(U22A-IN1+)") (class "Default")
      (node (ref "R113") (pin "2") (pinfunction "2_2") (pintype "input"))
      (node (ref "R122") (pin "2") (pinfunction "2_2") (pintype "input"))
      (node (ref "U22") (pin "3") (pinfunction "IN1+_3") (pintype "unspecified"))
    )
    (net (code "83") (name "Net-(U22B-IN2+)") (class "Default")
      (node (ref "R108") (pin "2") (pinfunction "2_2") (pintype "input"))
      (node (ref "U22") (pin "5") (pinfunction "IN2+_5") (pintype "unspecified"))
    )
    (net (code "84") (name "Net-(U22B-IN2-)") (class "Default")
      (node (ref "R109") (pin "1") (pinfunction "1_1") (pintype "input"))
      (node (ref "R120") (pin "2") (pinfunction "2_2") (pintype "input"))
      (node (ref "U22") (pin "6") (pinfunction "IN2-_6") (pintype "unspecified"))
    )
    (net (code "85") (name "Net-(U22B-OUT2)") (class "Default")
      (node (ref "R107") (pin "2") (pinfunction "2_2") (pintype "input"))
      (node (ref "R109") (pin "2") (pinfunction "2_2") (pintype "input"))
      (node (ref "R115") (pin "1") (pinfunction "1_1") (pintype "input"))
      (node (ref "U22") (pin "7") (pinfunction "OUT2_7") (pintype "output"))
    )
    (net (code "86") (name "Net-(U22C-IN3+)") (class "Default")
      (node (ref "R114") (pin "2") (pinfunction "2_2") (pintype "input"))
      (node (ref "R119") (pin "2") (pinfunction "2_2") (pintype "input"))
      (node (ref "U22") (pin "10") (pinfunction "IN3+_10") (pintype "unspecified"))
    )
    (net (code "87") (name "Net-(U22D-IN4+)") (class "Default")
      (node (ref "R112") (pin "2") (pinfunction "2_2") (pintype "input"))
      (node (ref "U22") (pin "12") (pinfunction "IN4+_12") (pintype "unspecified"))
    )
    (net (code "88") (name "Net-(U22D-IN4-)") (class "Default")
      (node (ref "R117") (pin "2") (pinfunction "2_2") (pintype "input"))
      (node (ref "R124") (pin "1") (pinfunction "1_1") (pintype "input"))
      (node (ref "U22") (pin "13") (pinfunction "IN4-_13") (pintype "unspecified"))
    )
    (net (code "89") (name "Net-(U22D-OUT4)") (class "Default")
      (node (ref "R110") (pin "1") (pinfunction "1_1") (pintype "input"))
      (node (ref "R111") (pin "2") (pinfunction "2_2") (pintype "input"))
      (node (ref "R124") (pin "2") (pinfunction "2_2") (pintype "input"))
      (node (ref "U22") (pin "14") (pinfunction "OUT4_14") (pintype "output"))
    )
    (net (code "90") (name "Net-(U23A-IN1+)") (class "Default")
      (node (ref "R131") (pin "2") (pinfunction "2_2") (pintype "input"))
      (node (ref "R140") (pin "2") (pinfunction "2_2") (pintype "input"))
      (node (ref "U23") (pin "3") (pinfunction "IN1+_3") (pintype "unspecified"))
    )
    (net (code "91") (name "Net-(U23B-IN2+)") (class "Default")
      (node (ref "R126") (pin "2") (pinfunction "2_2") (pintype "input"))
      (node (ref "U23") (pin "5") (pinfunction "IN2+_5") (pintype "unspecified"))
    )
    (net (code "92") (name "Net-(U23B-IN2-)") (class "Default")
      (node (ref "R127") (pin "1") (pinfunction "1_1") (pintype "input"))
      (node (ref "R138") (pin "2") (pinfunction "2_2") (pintype "input"))
      (node (ref "U23") (pin "6") (pinfunction "IN2-_6") (pintype "unspecified"))
    )
    (net (code "93") (name "Net-(U23B-OUT2)") (class "Default")
      (node (ref "R125") (pin "2") (pinfunction "2_2") (pintype "input"))
      (node (ref "R127") (pin "2") (pinfunction "2_2") (pintype "input"))
      (node (ref "R133") (pin "1") (pinfunction "1_1") (pintype "input"))
      (node (ref "U23") (pin "7") (pinfunction "OUT2_7") (pintype "output"))
    )
    (net (code "94") (name "Net-(U23C-IN3+)") (class "Default")
      (node (ref "R132") (pin "2") (pinfunction "2_2") (pintype "input"))
      (node (ref "R137") (pin "2") (pinfunction "2_2") (pintype "input"))
      (node (ref "U23") (pin "10") (pinfunction "IN3+_10") (pintype "unspecified"))
    )
    (net (code "95") (name "Net-(U23D-IN4+)") (class "Default")
      (node (ref "R130") (pin "2") (pinfunction "2_2") (pintype "input"))
      (node (ref "U23") (pin "12") (pinfunction "IN4+_12") (pintype "unspecified"))
    )
    (net (code "96") (name "Net-(U23D-IN4-)") (class "Default")
      (node (ref "R135") (pin "2") (pinfunction "2_2") (pintype "input"))
      (node (ref "R142") (pin "1") (pinfunction "1_1") (pintype "input"))
      (node (ref "U23") (pin "13") (pinfunction "IN4-_13") (pintype "unspecified"))
    )
    (net (code "97") (name "Net-(U23D-OUT4)") (class "Default")
      (node (ref "R128") (pin "1") (pinfunction "1_1") (pintype "input"))
      (node (ref "R129") (pin "2") (pinfunction "2_2") (pintype "input"))
      (node (ref "R142") (pin "2") (pinfunction "2_2") (pintype "input"))
      (node (ref "U23") (pin "14") (pinfunction "OUT4_14") (pintype "output"))
    )
    (net (code "98") (name "Net-(U24A-IN1+)") (class "Default")
      (node (ref "R149") (pin "2") (pinfunction "2_2") (pintype "input"))
      (node (ref "R158") (pin "2") (pinfunction "2_2") (pintype "input"))
      (node (ref "U24") (pin "3") (pinfunction "IN1+_3") (pintype "unspecified"))
    )
    (net (code "99") (name "Net-(U24B-IN2+)") (class "Default")
      (node (ref "R144") (pin "2") (pinfunction "2_2") (pintype "input"))
      (node (ref "U24") (pin "5") (pinfunction "IN2+_5") (pintype "unspecified"))
    )
    (net (code "100") (name "Net-(U24B-IN2-)") (class "Default")
      (node (ref "R145") (pin "1") (pinfunction "1_1") (pintype "input"))
      (node (ref "R156") (pin "2") (pinfunction "2_2") (pintype "input"))
      (node (ref "U24") (pin "6") (pinfunction "IN2-_6") (pintype "unspecified"))
    )
    (net (code "101") (name "Net-(U24B-OUT2)") (class "Default")
      (node (ref "R143") (pin "2") (pinfunction "2_2") (pintype "input"))
      (node (ref "R145") (pin "2") (pinfunction "2_2") (pintype "input"))
      (node (ref "R151") (pin "1") (pinfunction "1_1") (pintype "input"))
      (node (ref "U24") (pin "7") (pinfunction "OUT2_7") (pintype "output"))
    )
    (net (code "102") (name "Net-(U24C-IN3+)") (class "Default")
      (node (ref "R150") (pin "2") (pinfunction "2_2") (pintype "input"))
      (node (ref "R155") (pin "2") (pinfunction "2_2") (pintype "input"))
      (node (ref "U24") (pin "10") (pinfunction "IN3+_10") (pintype "unspecified"))
    )
    (net (code "103") (name "Net-(U24D-IN4+)") (class "Default")
      (node (ref "R148") (pin "2") (pinfunction "2_2") (pintype "input"))
      (node (ref "U24") (pin "12") (pinfunction "IN4+_12") (pintype "unspecified"))
    )
    (net (code "104") (name "Net-(U24D-IN4-)") (class "Default")
      (node (ref "R153") (pin "2") (pinfunction "2_2") (pintype "input"))
      (node (ref "R160") (pin "1") (pinfunction "1_1") (pintype "input"))
      (node (ref "U24") (pin "13") (pinfunction "IN4-_13") (pintype "unspecified"))
    )
    (net (code "105") (name "Net-(U24D-OUT4)") (class "Default")
      (node (ref "R146") (pin "1") (pinfunction "1_1") (pintype "input"))
      (node (ref "R147") (pin "2") (pinfunction "2_2") (pintype "input"))
      (node (ref "R160") (pin "2") (pinfunction "2_2") (pintype "input"))
      (node (ref "U24") (pin "14") (pinfunction "OUT4_14") (pintype "output"))
    )
    (net (code "106") (name "P0") (class "Default")
      (node (ref "R108") (pin "1") (pinfunction "1_1") (pintype "input"))
      (node (ref "R122") (pin "1") (pinfunction "1_1") (pintype "input"))
      (node (ref "R126") (pin "1") (pinfunction "1_1") (pintype "input"))
      (node (ref "R140") (pin "1") (pinfunction "1_1") (pintype "input"))
      (node (ref "R144") (pin "1") (pinfunction "1_1") (pintype "input"))
      (node (ref "R158") (pin "1") (pinfunction "1_1") (pintype "input"))
      (node (ref "R17") (pin "1") (pinfunction "1_1") (pintype "input"))
      (node (ref "R19") (pin "1") (pinfunction "1_1") (pintype "input"))
      (node (ref "R35") (pin "1") (pinfunction "1_1") (pintype "input"))
      (node (ref "R37") (pin "1") (pinfunction "1_1") (pintype "input"))
      (node (ref "R53") (pin "1") (pinfunction "1_1") (pintype "input"))
      (node (ref "R55") (pin "1") (pinfunction "1_1") (pintype "input"))
      (node (ref "R71") (pin "1") (pinfunction "1_1") (pintype "input"))
      (node (ref "R73") (pin "1") (pinfunction "1_1") (pintype "input"))
      (node (ref "R89") (pin "1") (pinfunction "1_1") (pintype "input"))
      (node (ref "R91") (pin "1") (pinfunction "1_1") (pintype "input"))
      (node (ref "U1") (pin "2") (pinfunction "WIPER_2") (pintype "bidirectional"))
    )
    (net (code "107") (name "P1") (class "Default")
      (node (ref "R102") (pin "1") (pinfunction "1_1") (pintype "input"))
      (node (ref "R112") (pin "1") (pinfunction "1_1") (pintype "input"))
      (node (ref "R119") (pin "1") (pinfunction "1_1") (pintype "input"))
      (node (ref "R130") (pin "1") (pinfunction "1_1") (pintype "input"))
      (node (ref "R137") (pin "1") (pinfunction "1_1") (pintype "input"))
      (node (ref "R148") (pin "1") (pinfunction "1_1") (pintype "input"))
      (node (ref "R155") (pin "1") (pinfunction "1_1") (pintype "input"))
      (node (ref "R26") (pin "1") (pinfunction "1_1") (pintype "input"))
      (node (ref "R28") (pin "1") (pinfunction "1_1") (pintype "input"))
      (node (ref "R44") (pin "1") (pinfunction "1_1") (pintype "input"))
      (node (ref "R46") (pin "1") (pinfunction "1_1") (pintype "input"))
      (node (ref "R62") (pin "1") (pinfunction "1_1") (pintype "input"))
      (node (ref "R64") (pin "1") (pinfunction "1_1") (pintype "input"))
      (node (ref "R80") (pin "1") (pinfunction "1_1") (pintype "input"))
      (node (ref "R82") (pin "1") (pinfunction "1_1") (pintype "input"))
      (node (ref "R99") (pin "1") (pinfunction "1_1") (pintype "input"))
      (node (ref "U2") (pin "2") (pinfunction "WIPER_2") (pintype "bidirectional"))
    )
    (net (code "108") (name "P2") (class "Default")
      (node (ref "U3") (pin "2") (pinfunction "WIPER_2") (pintype "bidirectional"))
    )
    (net (code "109") (name "P3") (class "Default")
      (node (ref "U4") (pin "2") (pinfunction "WIPER_2") (pintype "bidirectional"))
    )
    (net (code "110") (name "P4") (class "Default")
      (node (ref "U5") (pin "2") (pinfunction "WIPER_2") (pintype "bidirectional"))
    )
    (net (code "111") (name "P5") (class "Default")
      (node (ref "U6") (pin "2") (pinfunction "WIPER_2") (pintype "bidirectional"))
    )
    (net (code "112") (name "P6") (class "Default")
      (node (ref "U7") (pin "2") (pinfunction "WIPER_2") (pintype "bidirectional"))
    )
    (net (code "113") (name "P7") (class "Default")
      (node (ref "U8") (pin "2") (pinfunction "WIPER_2") (pintype "bidirectional"))
    )
    (net (code "114") (name "P8") (class "Default")
      (node (ref "U9") (pin "2") (pinfunction "WIPER_2") (pintype "bidirectional"))
    )
    (net (code "115") (name "P9") (class "Default")
      (node (ref "U10") (pin "2") (pinfunction "WIPER_2") (pintype "bidirectional"))
    )
    (net (code "116") (name "P10") (class "Default")
      (node (ref "U11") (pin "2") (pinfunction "WIPER_2") (pintype "bidirectional"))
    )
    (net (code "117") (name "P11") (class "Default")
      (node (ref "U12") (pin "2") (pinfunction "WIPER_2") (pintype "bidirectional"))
    )
    (net (code "118") (name "P12") (class "Default")
      (node (ref "U13") (pin "2") (pinfunction "WIPER_2") (pintype "bidirectional"))
    )
    (net (code "119") (name "P13") (class "Default")
      (node (ref "U14") (pin "2") (pinfunction "WIPER_2") (pintype "bidirectional"))
    )
    (net (code "120") (name "P14") (class "Default")
      (node (ref "U15") (pin "2") (pinfunction "WIPER_2") (pintype "bidirectional"))
    )
    (net (code "121") (name "P15") (class "Default")
      (node (ref "U16") (pin "2") (pinfunction "WIPER_2") (pintype "bidirectional"))
    )
    (net (code "122") (name "unconnected-(U1-DUMMY_TERMINAL-PadL1)") (class "Default")
      (node (ref "U1") (pin "L1") (pinfunction "DUMMY_TERMINAL_L1") (pintype "bidirectional+no_connect"))
    )
    (net (code "123") (name "unconnected-(U2-DUMMY_TERMINAL-PadL1)") (class "Default")
      (node (ref "U2") (pin "L1") (pinfunction "DUMMY_TERMINAL_L1") (pintype "bidirectional+no_connect"))
    )
    (net (code "124") (name "unconnected-(U3-DUMMY_TERMINAL-PadL1)") (class "Default")
      (node (ref "U3") (pin "L1") (pinfunction "DUMMY_TERMINAL_L1") (pintype "bidirectional+no_connect"))
    )
    (net (code "125") (name "unconnected-(U4-DUMMY_TERMINAL-PadL1)") (class "Default")
      (node (ref "U4") (pin "L1") (pinfunction "DUMMY_TERMINAL_L1") (pintype "bidirectional+no_connect"))
    )
    (net (code "126") (name "unconnected-(U5-DUMMY_TERMINAL-PadL1)") (class "Default")
      (node (ref "U5") (pin "L1") (pinfunction "DUMMY_TERMINAL_L1") (pintype "bidirectional+no_connect"))
    )
    (net (code "127") (name "unconnected-(U6-DUMMY_TERMINAL-PadL1)") (class "Default")
      (node (ref "U6") (pin "L1") (pinfunction "DUMMY_TERMINAL_L1") (pintype "bidirectional+no_connect"))
    )
    (net (code "128") (name "unconnected-(U7-DUMMY_TERMINAL-PadL1)") (class "Default")
      (node (ref "U7") (pin "L1") (pinfunction "DUMMY_TERMINAL_L1") (pintype "bidirectional+no_connect"))
    )
    (net (code "129") (name "unconnected-(U8-DUMMY_TERMINAL-PadL1)") (class "Default")
      (node (ref "U8") (pin "L1") (pinfunction "DUMMY_TERMINAL_L1") (pintype "bidirectional+no_connect"))
    )
    (net (code "130") (name "unconnected-(U9-DUMMY_TERMINAL-PadL1)") (class "Default")
      (node (ref "U9") (pin "L1") (pinfunction "DUMMY_TERMINAL_L1") (pintype "bidirectional+no_connect"))
    )
    (net (code "131") (name "unconnected-(U10-DUMMY_TERMINAL-PadL1)") (class "Default")
      (node (ref "U10") (pin "L1") (pinfunction "DUMMY_TERMINAL_L1") (pintype "bidirectional+no_connect"))
    )
    (net (code "132") (name "unconnected-(U11-DUMMY_TERMINAL-PadL1)") (class "Default")
      (node (ref "U11") (pin "L1") (pinfunction "DUMMY_TERMINAL_L1") (pintype "bidirectional+no_connect"))
    )
    (net (code "133") (name "unconnected-(U12-DUMMY_TERMINAL-PadL1)") (class "Default")
      (node (ref "U12") (pin "L1") (pinfunction "DUMMY_TERMINAL_L1") (pintype "bidirectional+no_connect"))
    )
    (net (code "134") (name "unconnected-(U13-DUMMY_TERMINAL-PadL1)") (class "Default")
      (node (ref "U13") (pin "L1") (pinfunction "DUMMY_TERMINAL_L1") (pintype "bidirectional+no_connect"))
    )
    (net (code "135") (name "unconnected-(U14-DUMMY_TERMINAL-PadL1)") (class "Default")
      (node (ref "U14") (pin "L1") (pinfunction "DUMMY_TERMINAL_L1") (pintype "bidirectional+no_connect"))
    )
    (net (code "136") (name "unconnected-(U15-DUMMY_TERMINAL-PadL1)") (class "Default")
      (node (ref "U15") (pin "L1") (pinfunction "DUMMY_TERMINAL_L1") (pintype "bidirectional+no_connect"))
    )
    (net (code "137") (name "unconnected-(U16-DUMMY_TERMINAL-PadL1)") (class "Default")
      (node (ref "U16") (pin "L1") (pinfunction "DUMMY_TERMINAL_L1") (pintype "bidirectional+no_connect"))
    )
  )
)
